# RelayBoard.net
KiCad netlist of a schematic drawn in EAGLE
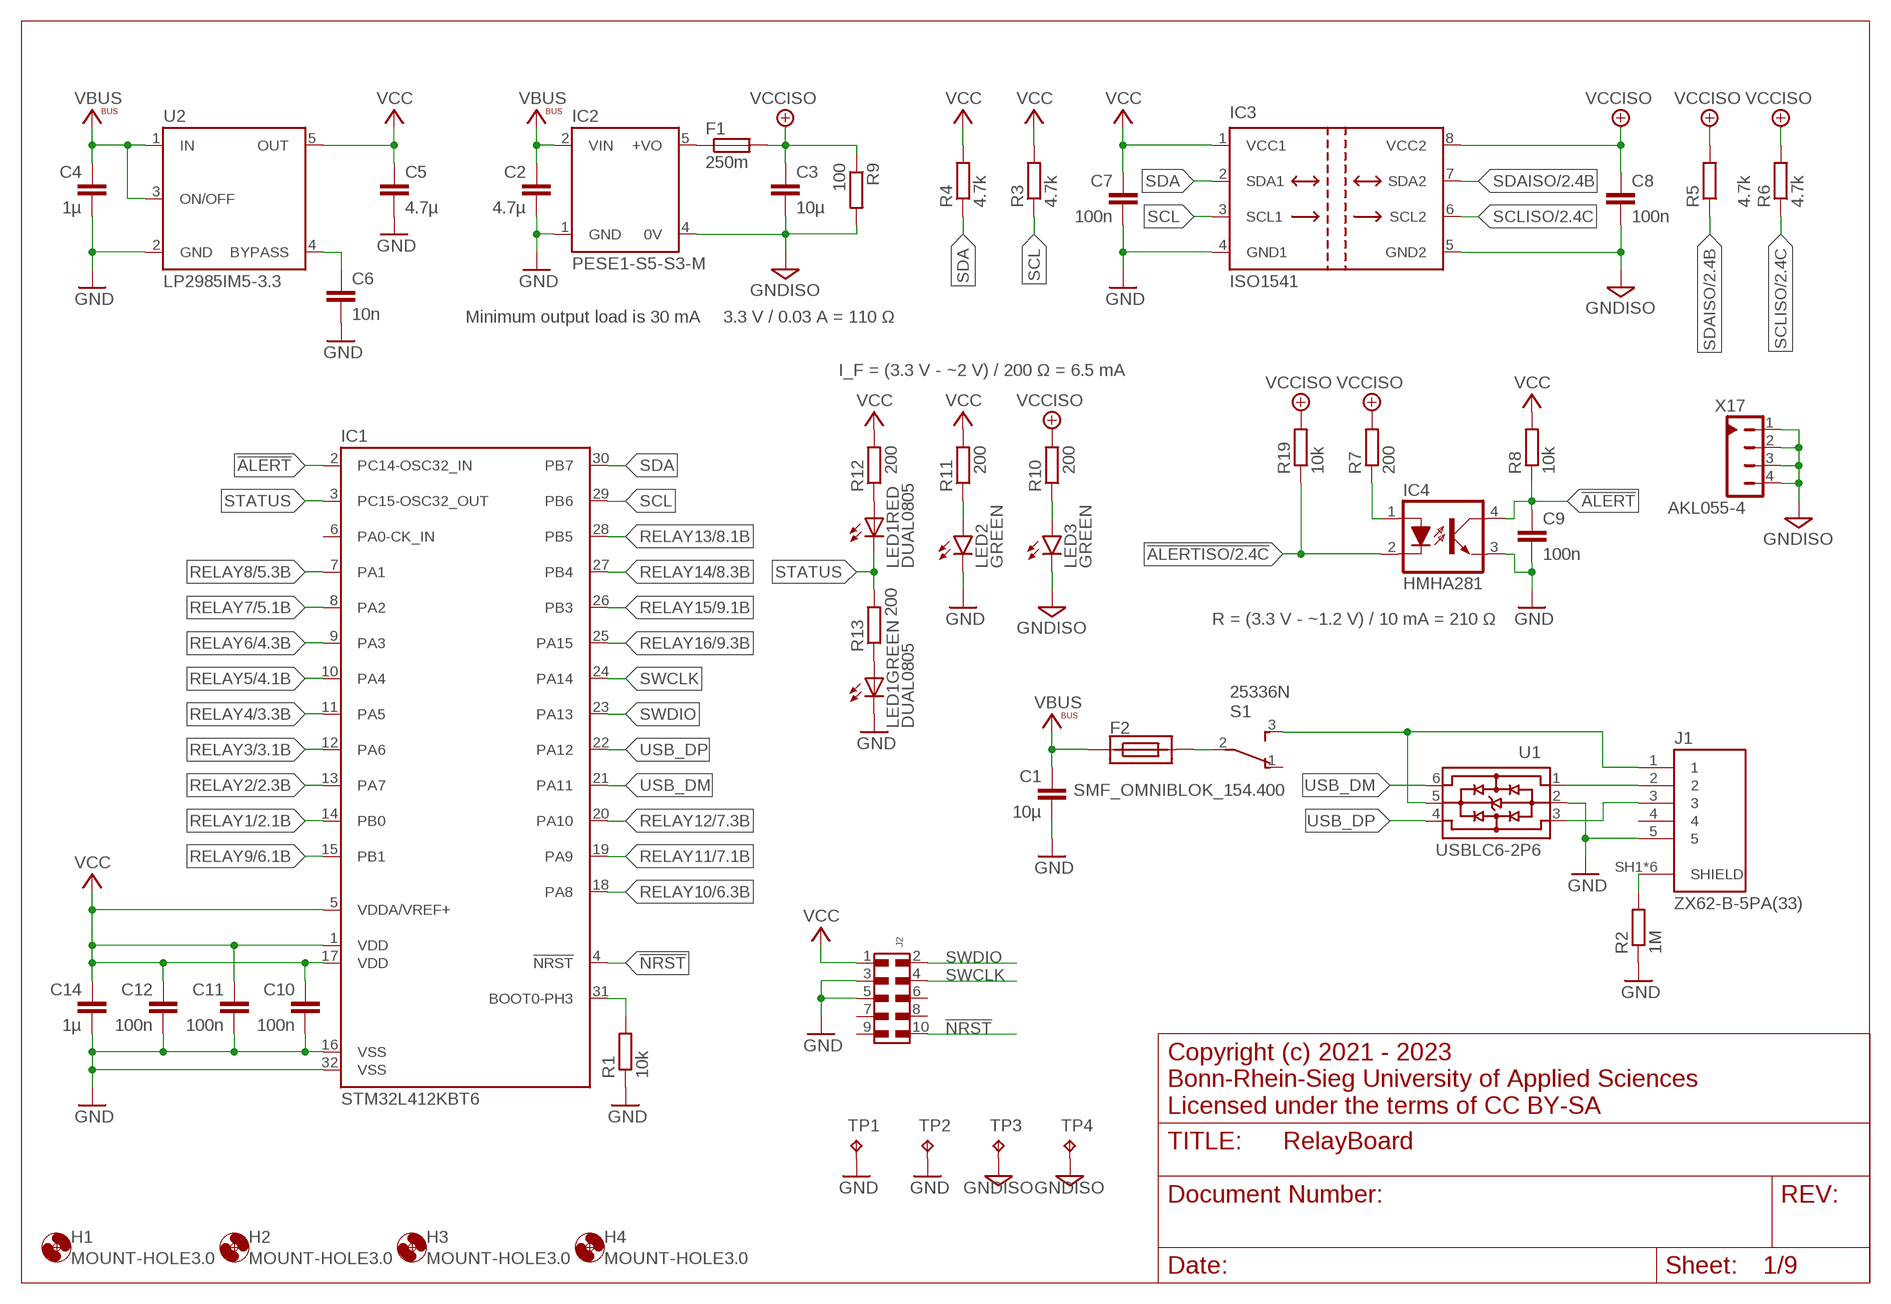
[diagram p0: schematic, sheet 1]
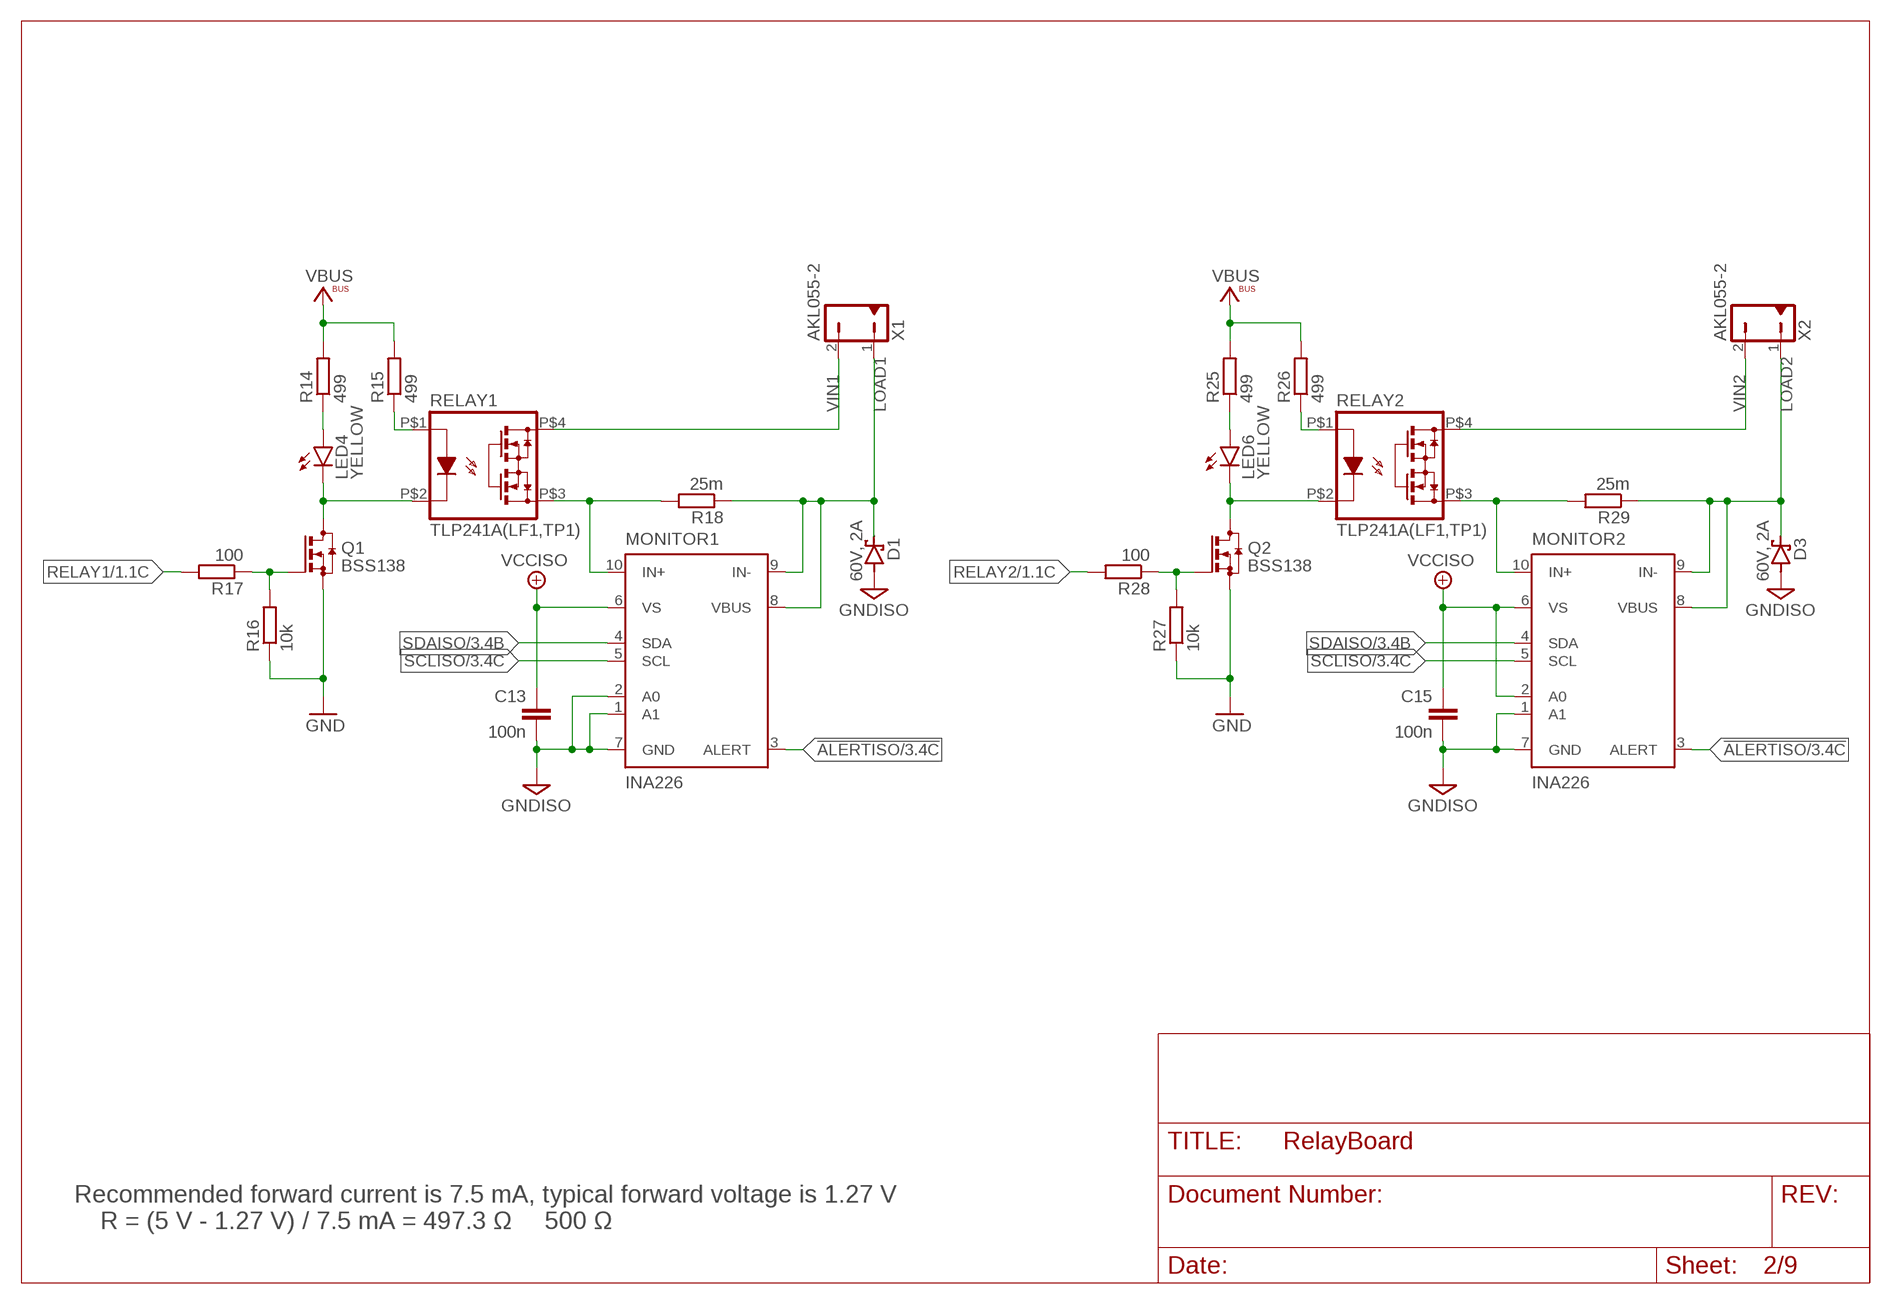
[diagram p1: schematic, sheet 2]
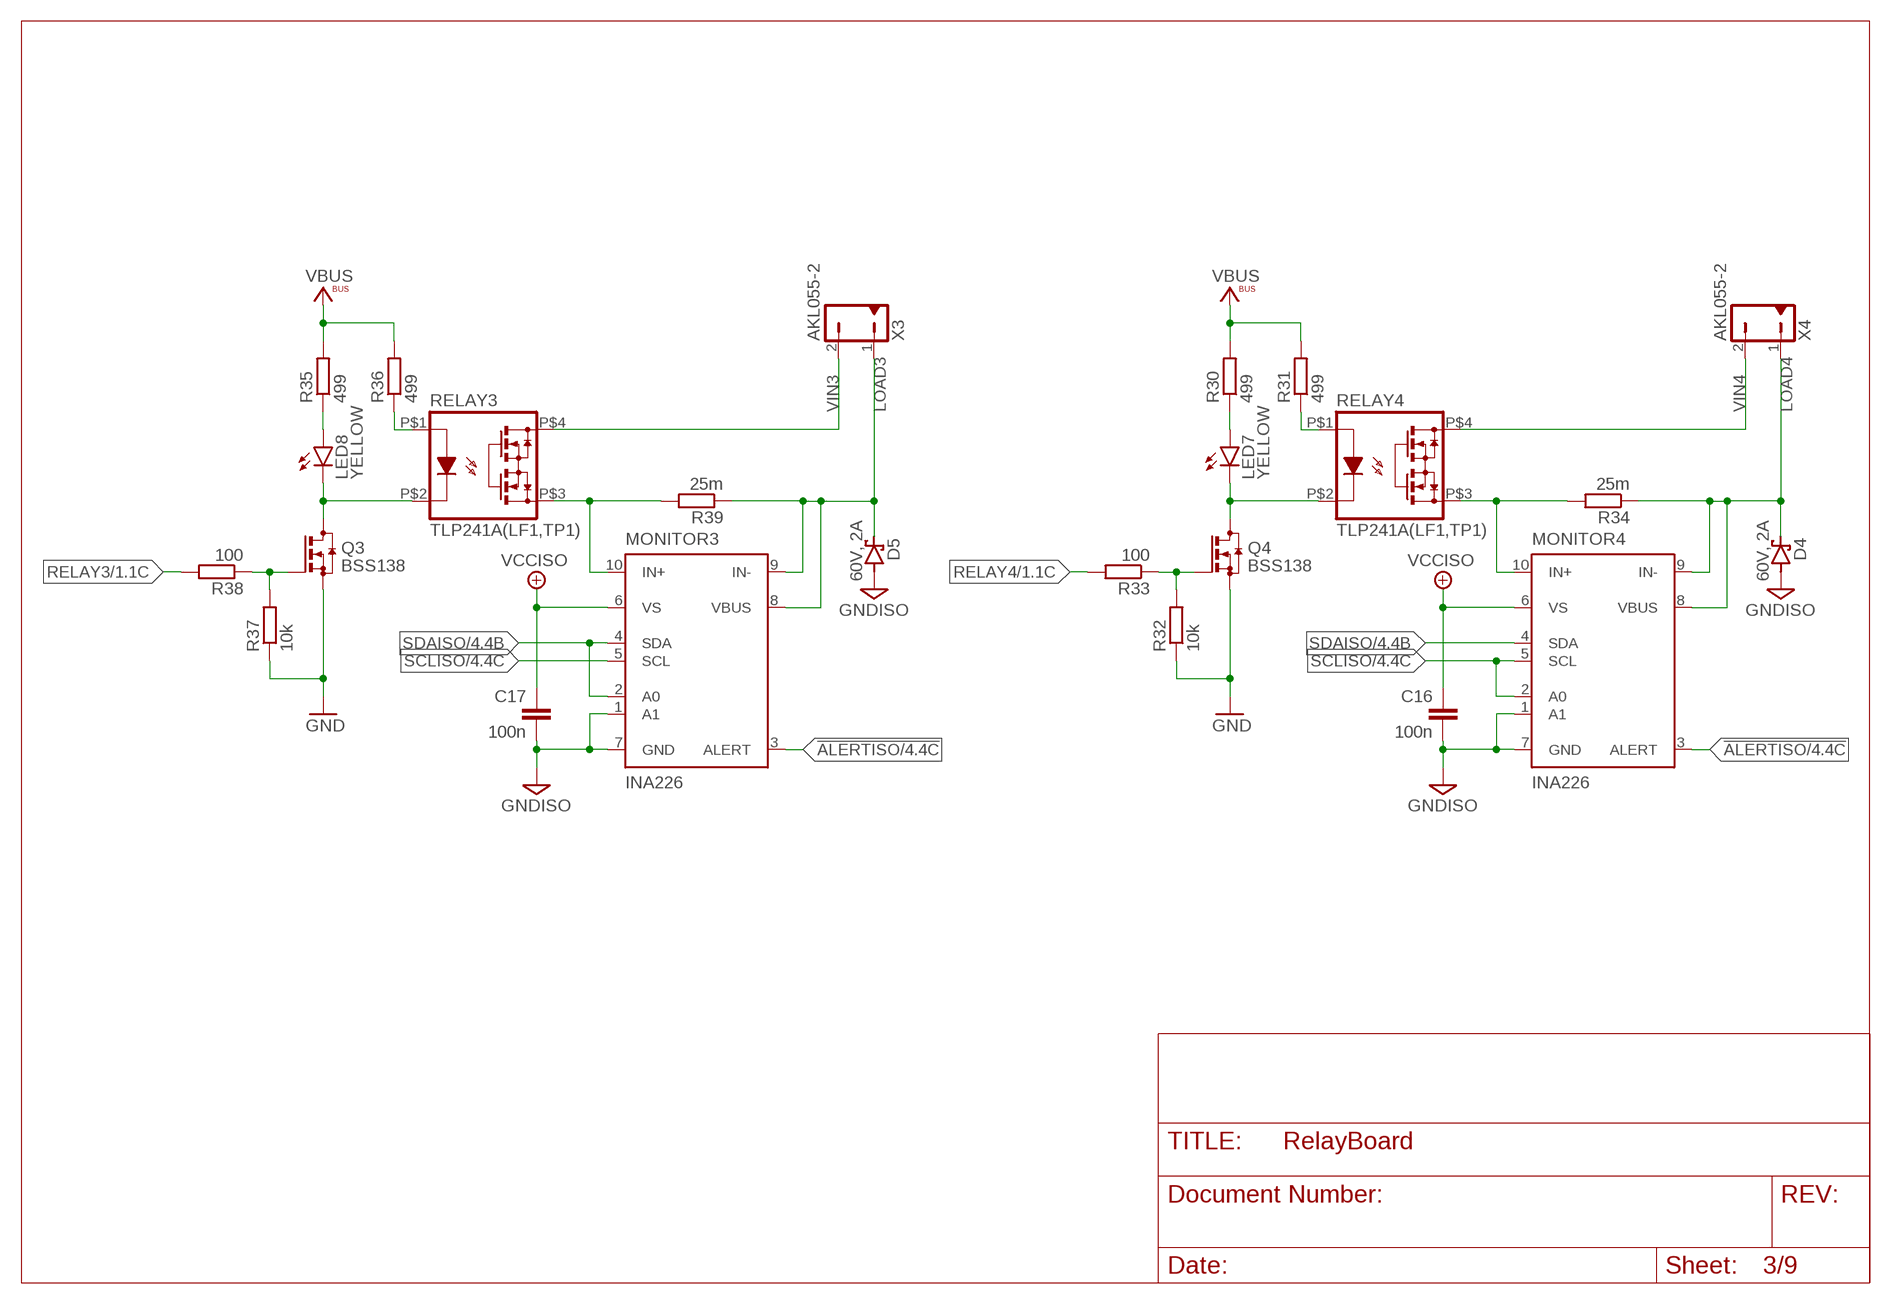
[diagram p2: schematic, sheet 3]
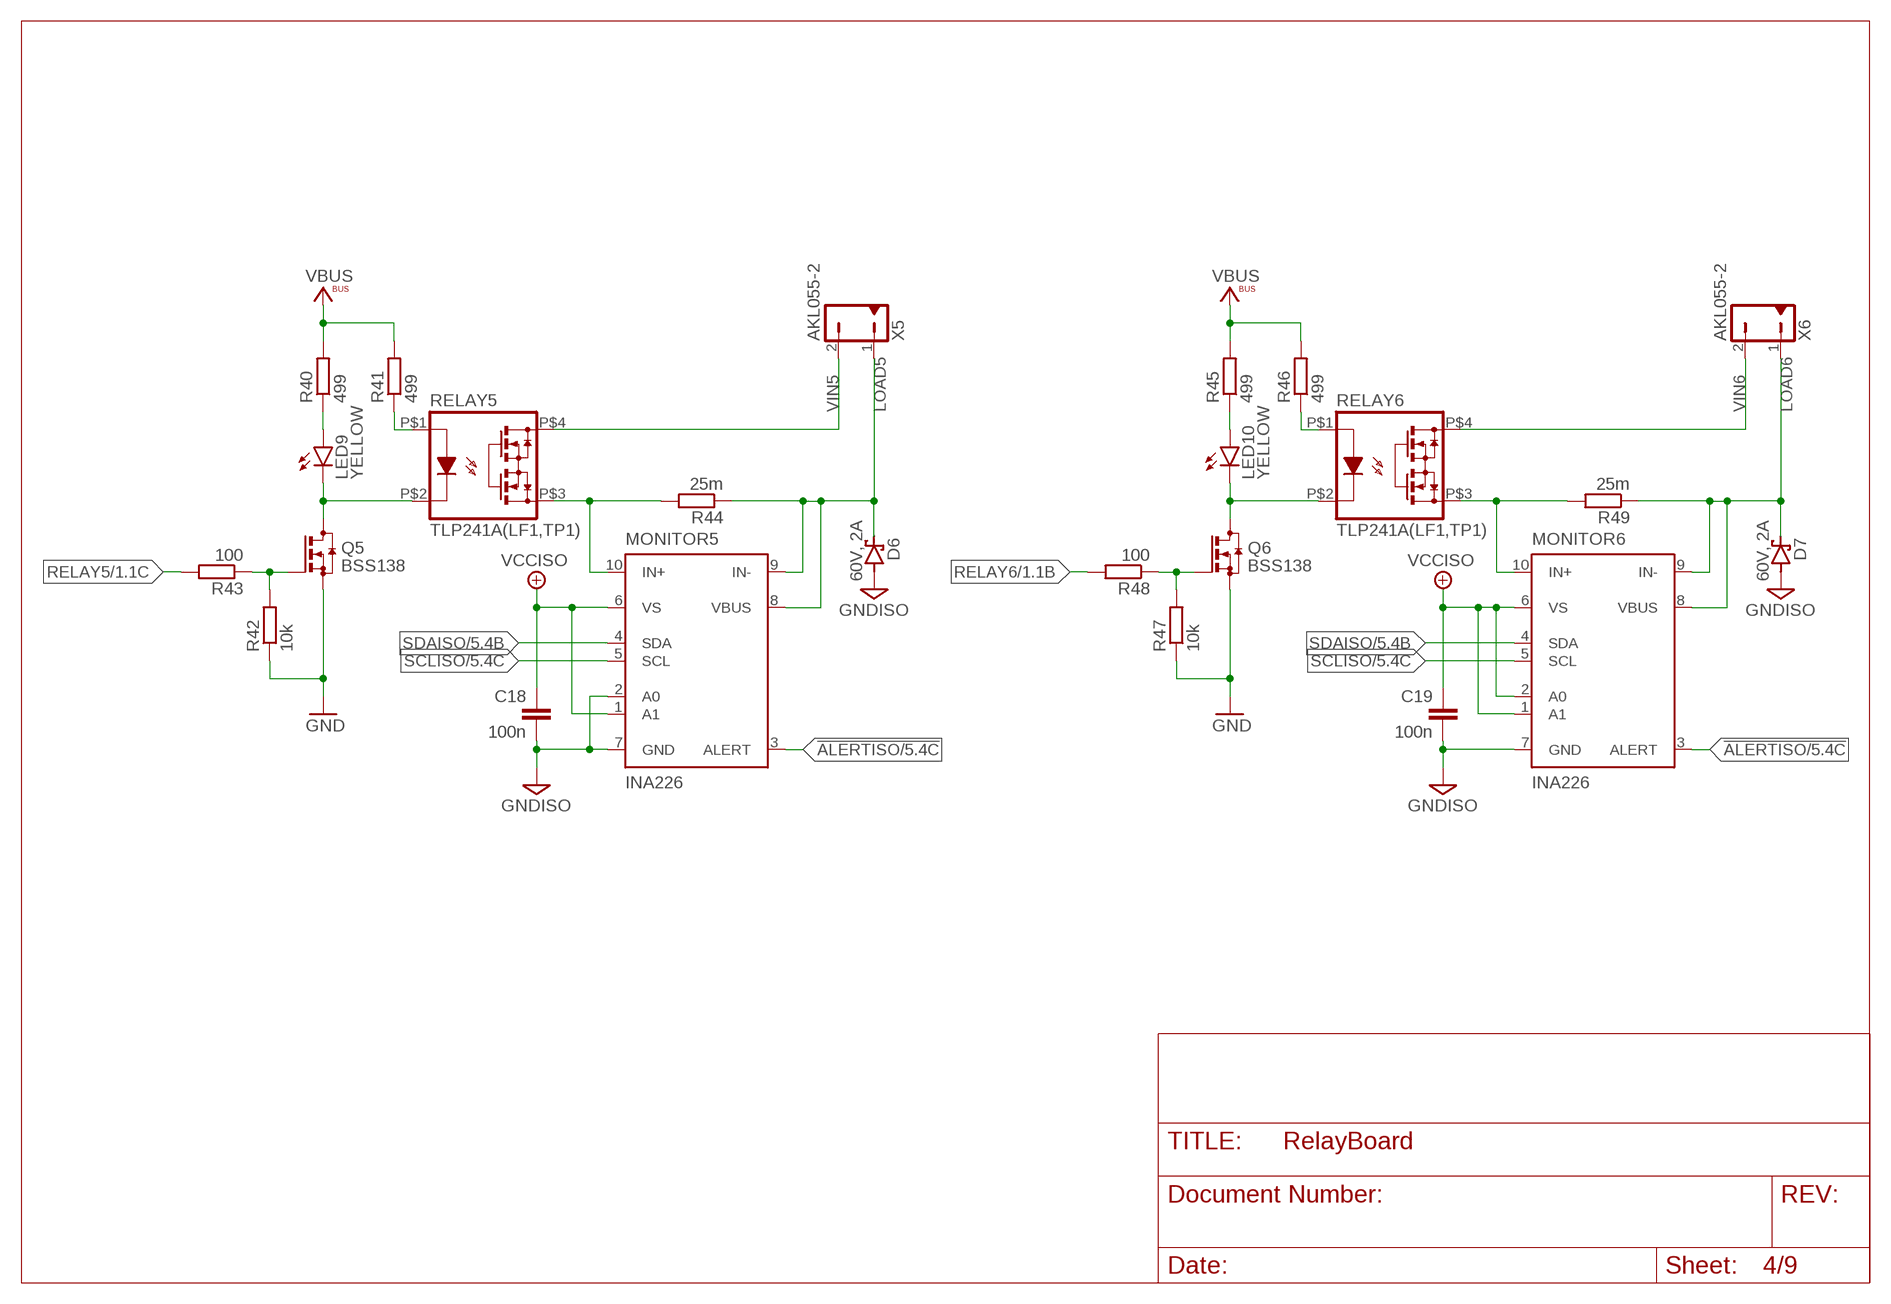
[diagram p3: schematic, sheet 4]
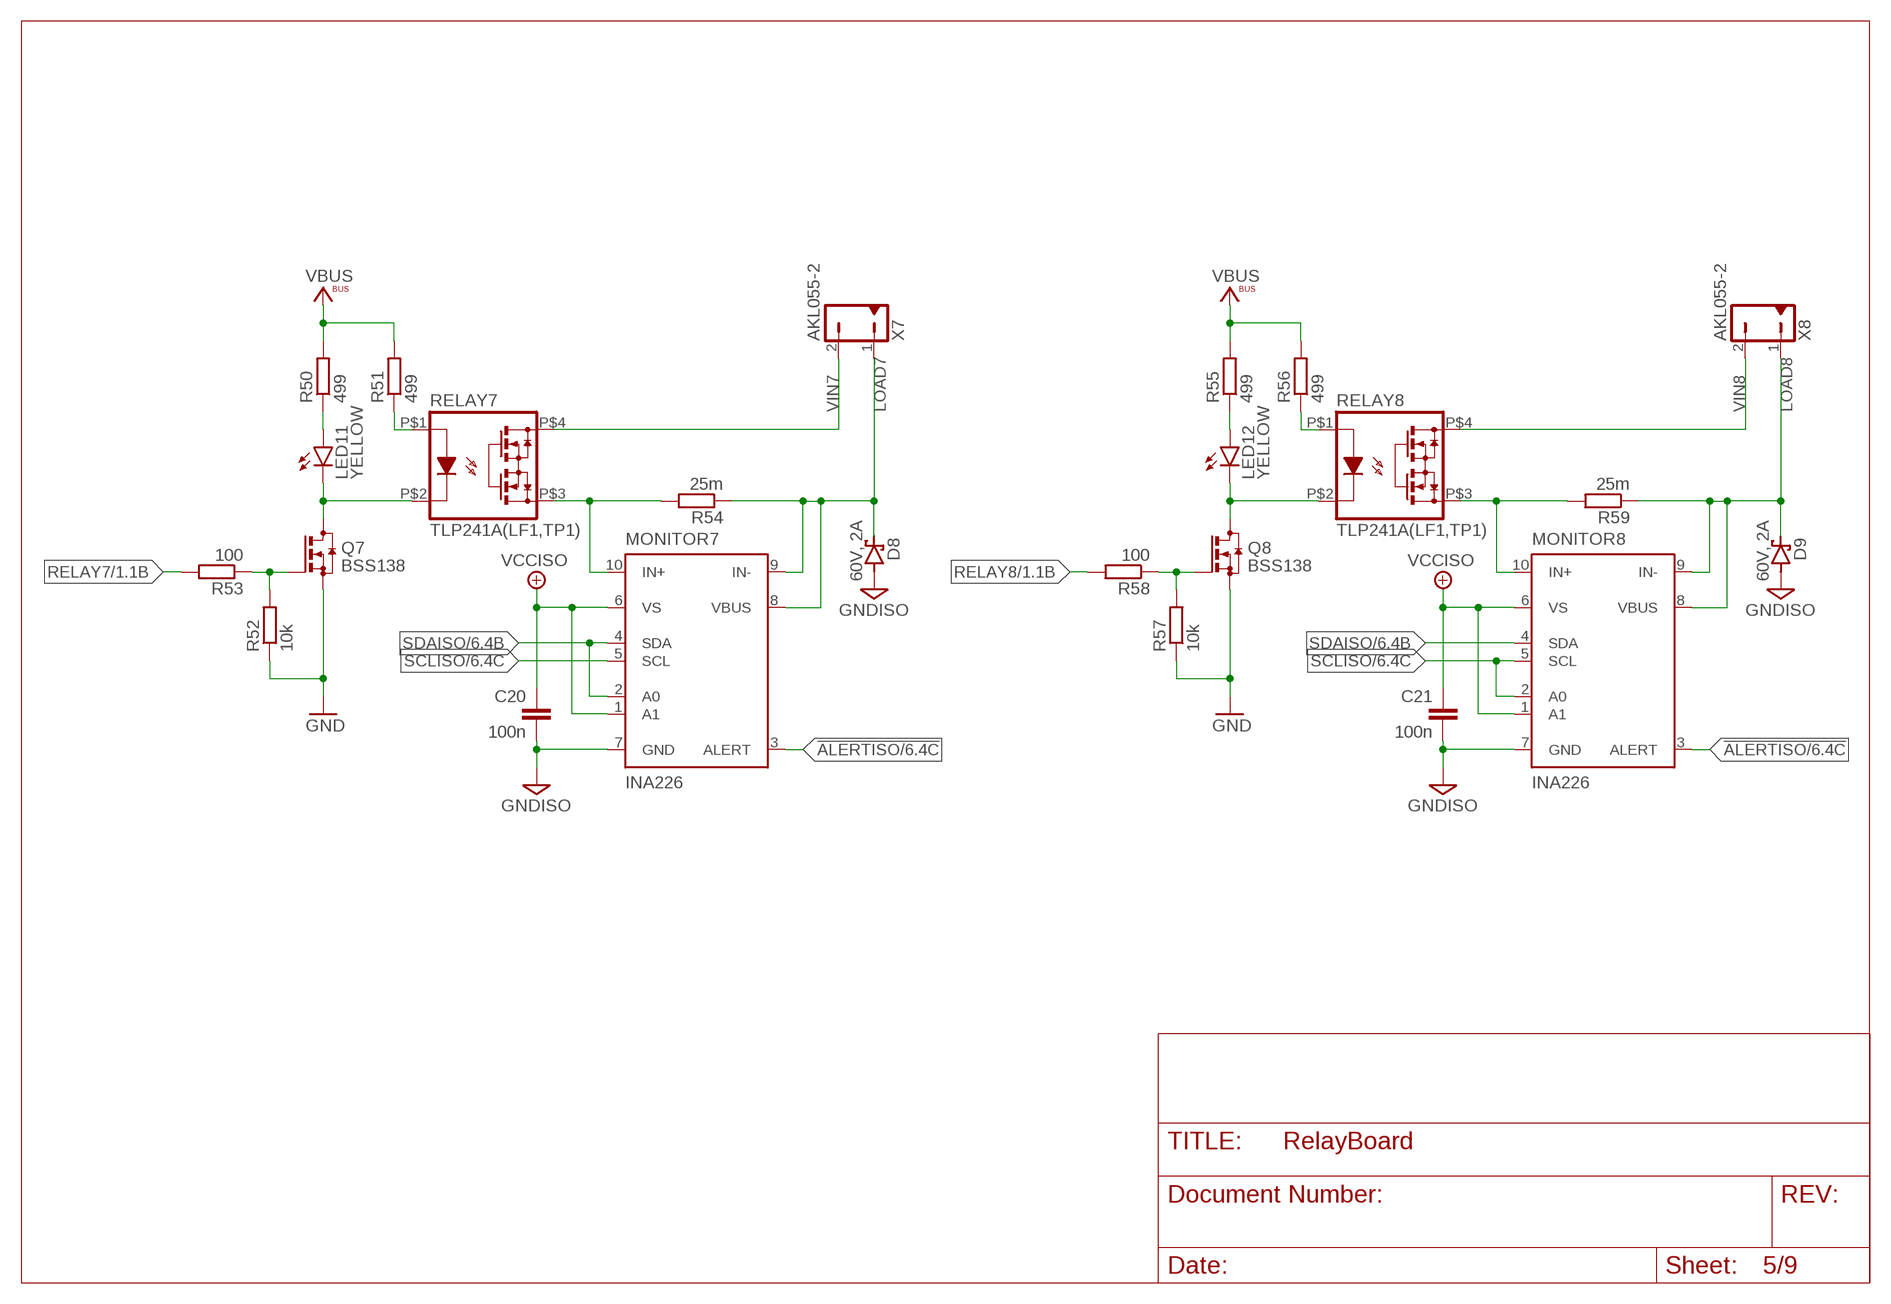
[diagram p4: schematic, sheet 5]
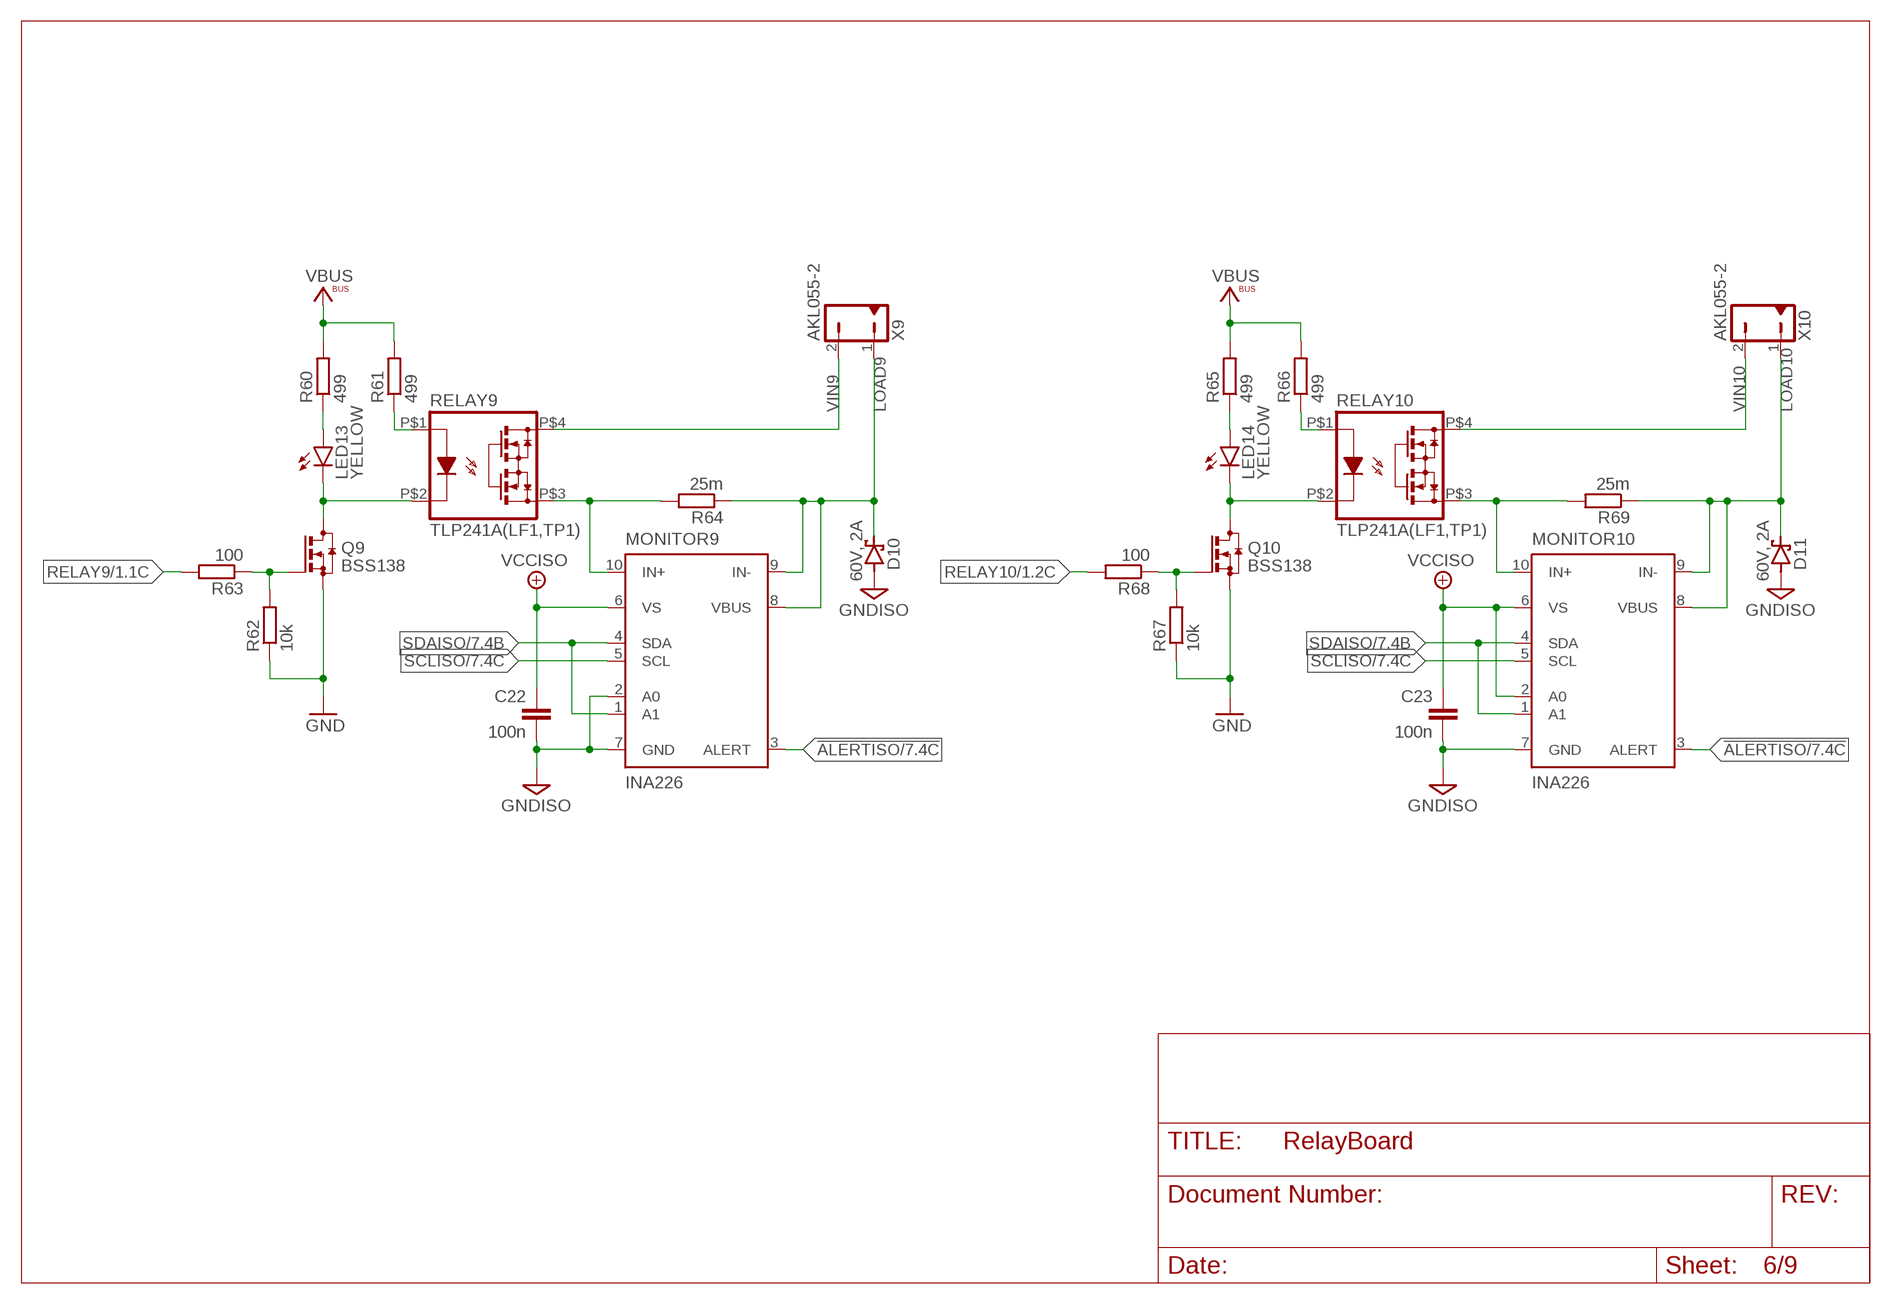
[diagram p5: schematic, sheet 6]
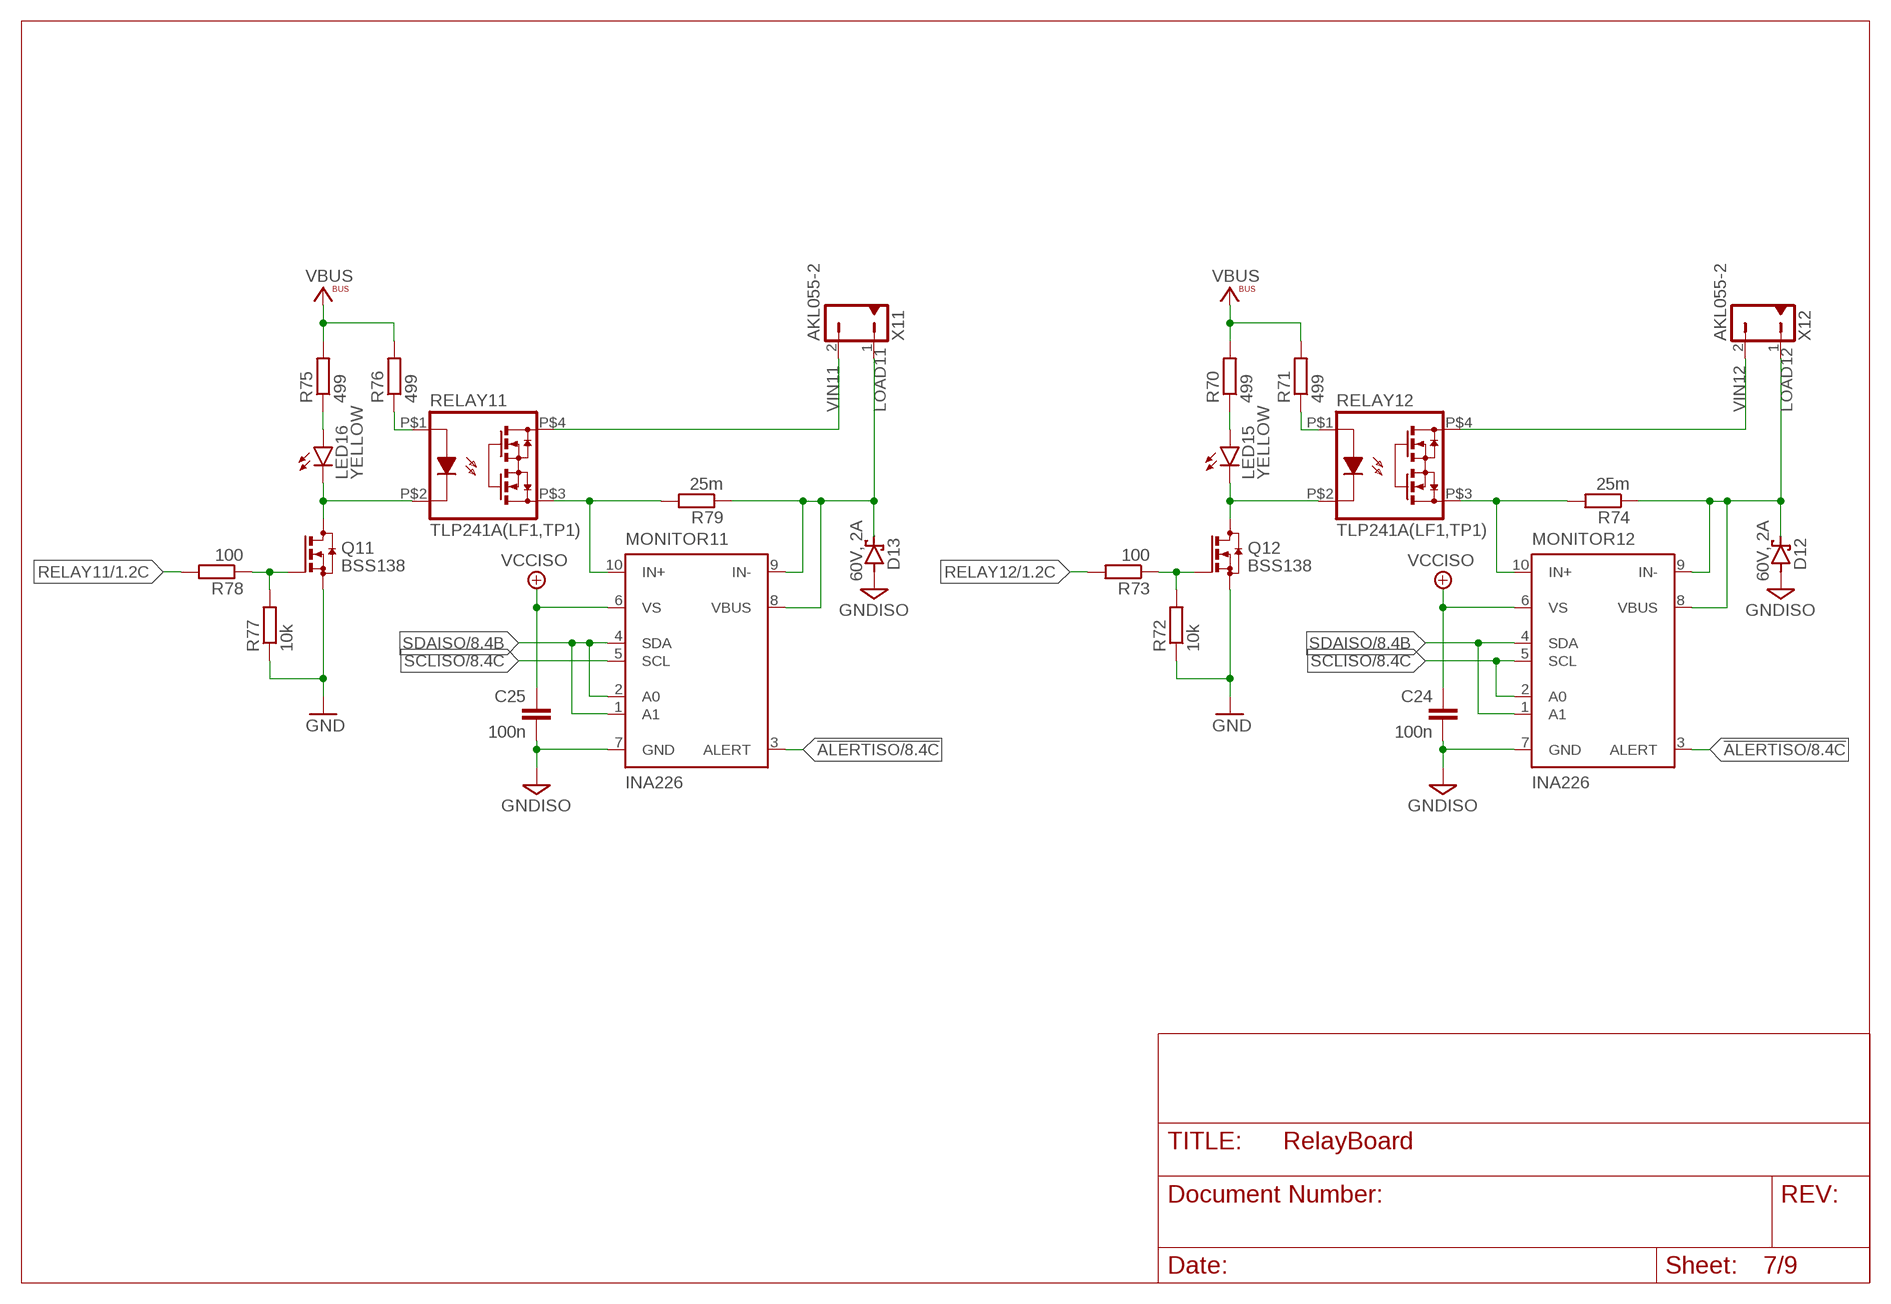
[diagram p6: schematic, sheet 7]
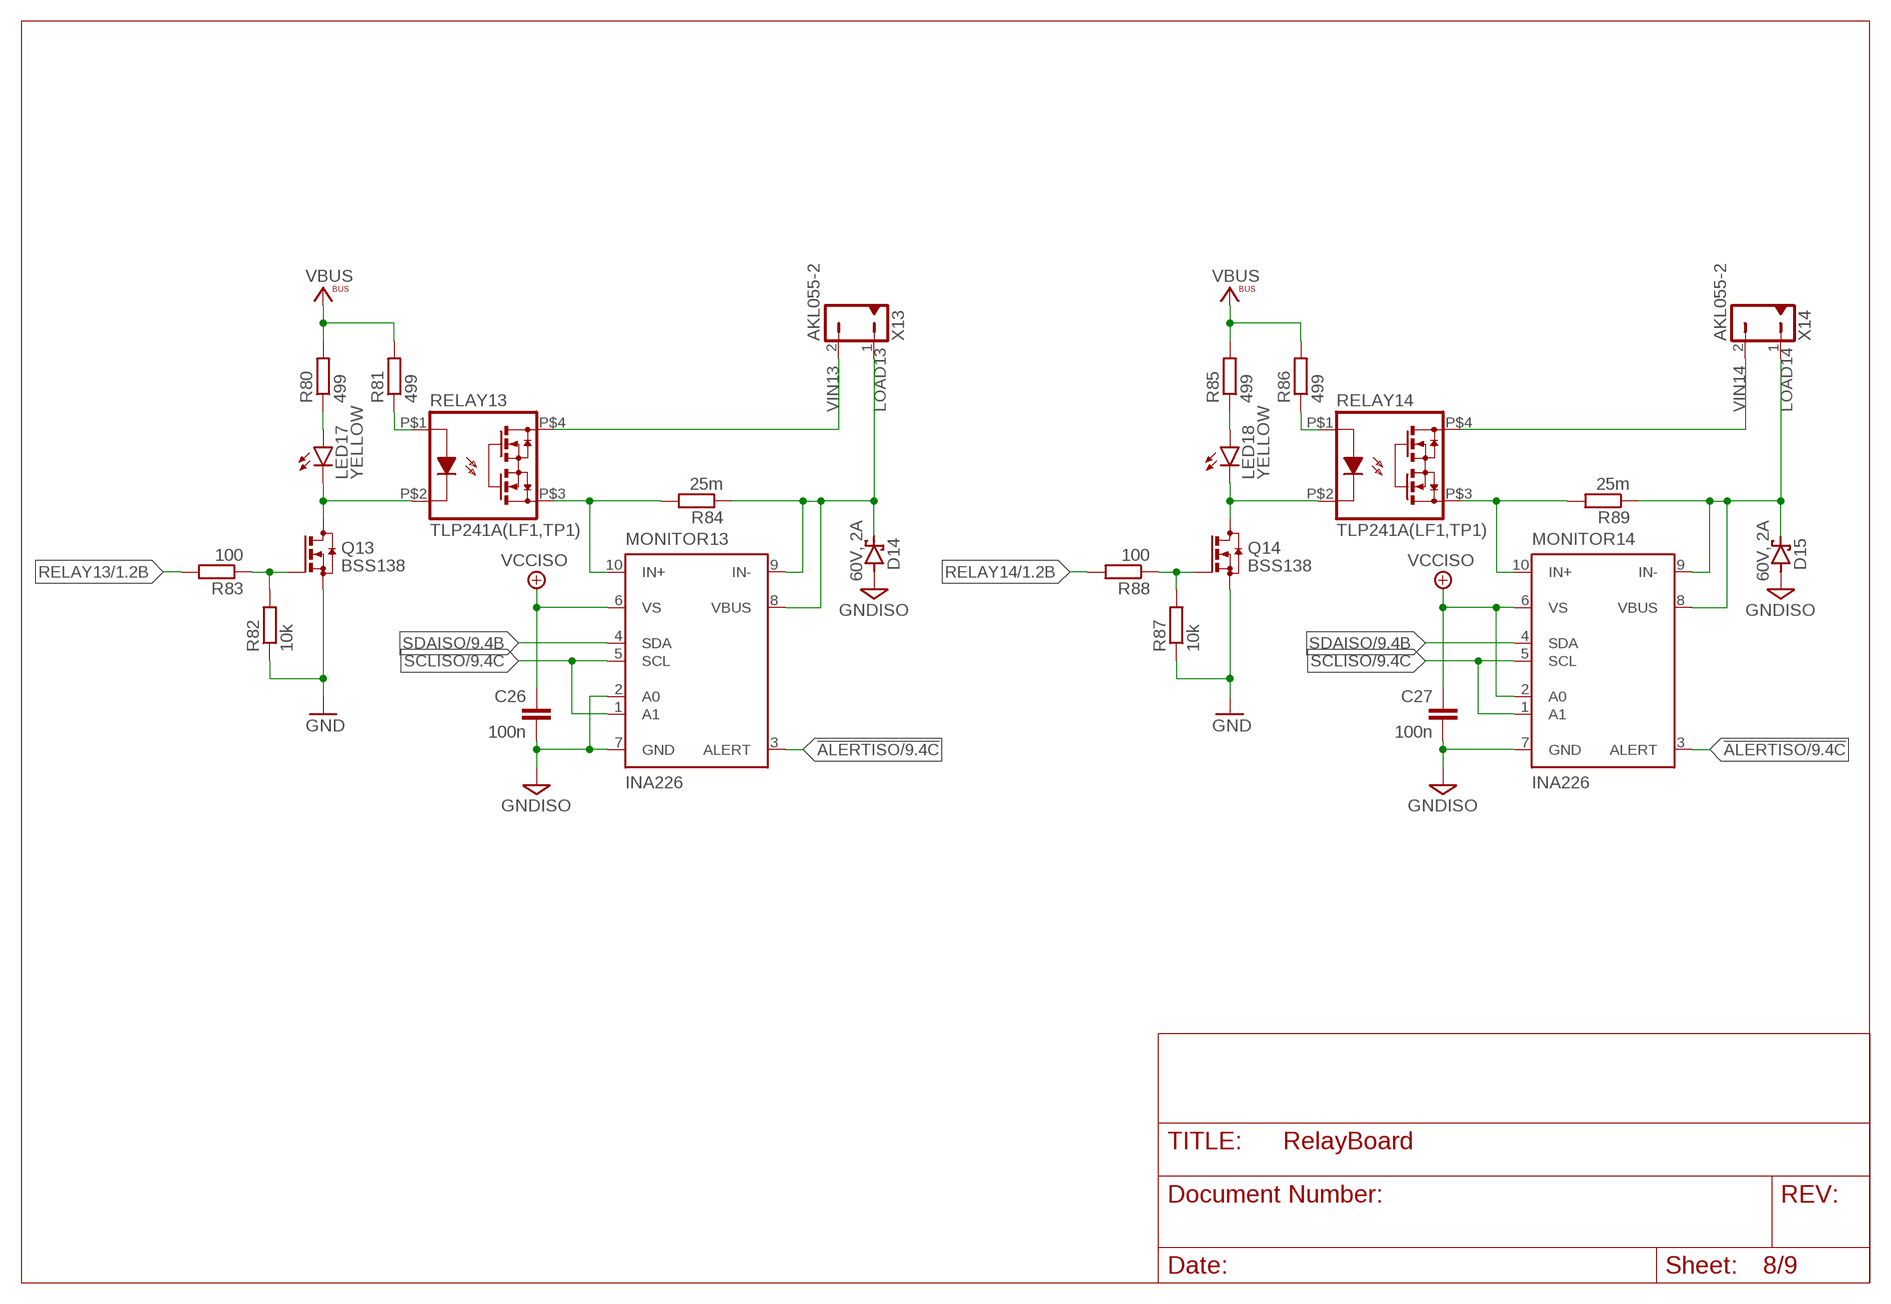
[diagram p7: schematic, sheet 8]
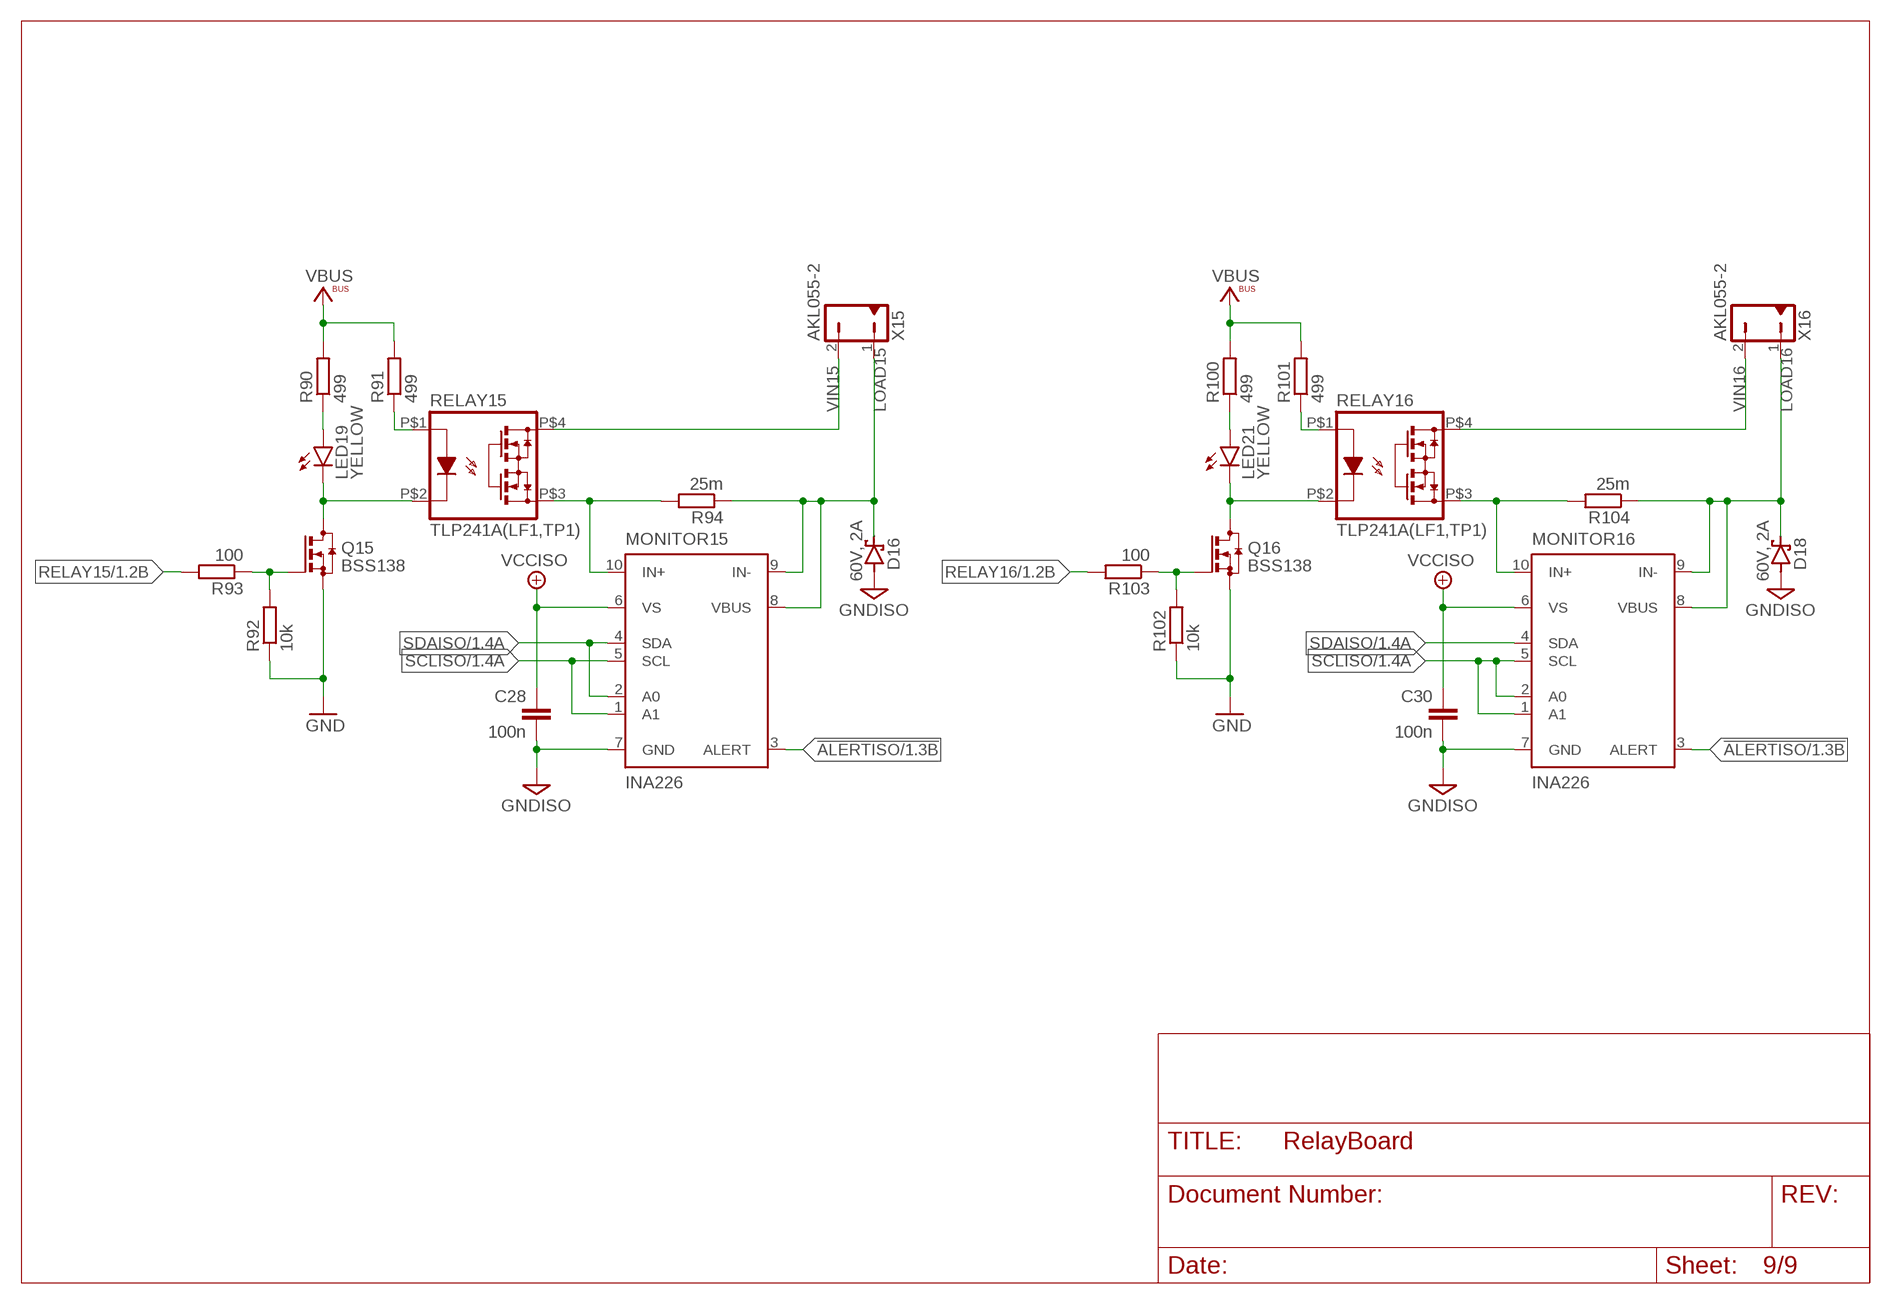
[diagram p8: schematic, sheet 9]

(export (version "E")
  (design (tool "Eeschema 10.0.6"))
  (components
    (comp (ref "C13")
      (value "100n")
      (footprint "eagle-import:C0603")
      (libsource (lib "eagle-import") (part "C-EUC0603"))
    )
    (comp (ref "C15")
      (value "100n")
      (footprint "eagle-import:C0603")
      (libsource (lib "eagle-import") (part "C-EUC0603"))
    )
    (comp (ref "D1")
      (value "60V, 2A")
      (footprint "eagle-import:SMB")
      (libsource (lib "eagle-import") (part "SCHOTTKY-DIODESMD"))
    )
    (comp (ref "D3")
      (value "60V, 2A")
      (footprint "eagle-import:SMB")
      (libsource (lib "eagle-import") (part "SCHOTTKY-DIODESMD"))
    )
    (comp (ref "LED4")
      (value "YELLOW")
      (footprint "eagle-import:CHIPLED_0805")
      (libsource (lib "eagle-import") (part "LEDCHIPLED_0805"))
    )
    (comp (ref "LED6")
      (value "YELLOW")
      (footprint "eagle-import:CHIPLED_0805")
      (libsource (lib "eagle-import") (part "LEDCHIPLED_0805"))
    )
    (comp (ref "MONITOR1")
      (value "INA226")
      (footprint "eagle-import:MSOP10")
      (libsource (lib "eagle-import") (part "INA226"))
    )
    (comp (ref "MONITOR2")
      (value "INA226")
      (footprint "eagle-import:MSOP10")
      (libsource (lib "eagle-import") (part "INA226"))
    )
    (comp (ref "Q1")
      (value "BSS138")
      (footprint "eagle-import:SOT23")
      (libsource (lib "eagle-import") (part "BSS138"))
    )
    (comp (ref "Q2")
      (value "BSS138")
      (footprint "eagle-import:SOT23")
      (libsource (lib "eagle-import") (part "BSS138"))
    )
    (comp (ref "R14")
      (value "499")
      (footprint "eagle-import:R0603")
      (libsource (lib "eagle-import") (part "R-EU_R0603"))
    )
    (comp (ref "R15")
      (value "499")
      (footprint "eagle-import:R0603")
      (libsource (lib "eagle-import") (part "R-EU_R0603"))
    )
    (comp (ref "R16")
      (value "10k")
      (footprint "eagle-import:R0603")
      (libsource (lib "eagle-import") (part "R-EU_R0603"))
    )
    (comp (ref "R17")
      (value "100")
      (footprint "eagle-import:R0603")
      (libsource (lib "eagle-import") (part "R-EU_R0603"))
    )
    (comp (ref "R18")
      (value "25m")
      (footprint "eagle-import:R1206")
      (libsource (lib "eagle-import") (part "R-EU_R1206"))
    )
    (comp (ref "R25")
      (value "499")
      (footprint "eagle-import:R0603")
      (libsource (lib "eagle-import") (part "R-EU_R0603"))
    )
    (comp (ref "R26")
      (value "499")
      (footprint "eagle-import:R0603")
      (libsource (lib "eagle-import") (part "R-EU_R0603"))
    )
    (comp (ref "R27")
      (value "10k")
      (footprint "eagle-import:R0603")
      (libsource (lib "eagle-import") (part "R-EU_R0603"))
    )
    (comp (ref "R28")
      (value "100")
      (footprint "eagle-import:R0603")
      (libsource (lib "eagle-import") (part "R-EU_R0603"))
    )
    (comp (ref "R29")
      (value "25m")
      (footprint "eagle-import:R1206")
      (libsource (lib "eagle-import") (part "R-EU_R1206"))
    )
    (comp (ref "RELAY1")
      (value "TLP241A(LF1,TP1)")
      (footprint "eagle-import:TP1_5")
      (libsource (lib "eagle-import") (part "TLP241A(?)LF1,TP1"))
    )
    (comp (ref "RELAY2")
      (value "TLP241A(LF1,TP1)")
      (footprint "eagle-import:TP1_5")
      (libsource (lib "eagle-import") (part "TLP241A(?)LF1,TP1"))
    )
    (comp (ref "X1")
      (value "AKL055-2")
      (footprint "eagle-import:AKL055-2")
      (libsource (lib "eagle-import") (part "AKL055-2"))
    )
    (comp (ref "X2")
      (value "AKL055-2")
      (footprint "eagle-import:AKL055-2")
      (libsource (lib "eagle-import") (part "AKL055-2"))
    )
    (comp (ref "C1")
      (value "10µ")
      (footprint "eagle-import:C0805")
      (libsource (lib "eagle-import") (part "C-EUC0805"))
    )
    (comp (ref "C2")
      (value "4.7µ")
      (footprint "eagle-import:C0805")
      (libsource (lib "eagle-import") (part "C-EUC0805"))
    )
    (comp (ref "C3")
      (value "10µ")
      (footprint "eagle-import:C0805")
      (libsource (lib "eagle-import") (part "C-EUC0805"))
    )
    (comp (ref "C4")
      (value "1µ")
      (footprint "eagle-import:C0805")
      (libsource (lib "eagle-import") (part "C-EUC0805"))
    )
    (comp (ref "C5")
      (value "4.7µ")
      (footprint "eagle-import:C0805")
      (libsource (lib "eagle-import") (part "C-EUC0805"))
    )
    (comp (ref "C6")
      (value "10n")
      (footprint "eagle-import:C0603")
      (libsource (lib "eagle-import") (part "C-EUC0603"))
    )
    (comp (ref "C7")
      (value "100n")
      (footprint "eagle-import:C0603")
      (libsource (lib "eagle-import") (part "C-EUC0603"))
    )
    (comp (ref "C8")
      (value "100n")
      (footprint "eagle-import:C0603")
      (libsource (lib "eagle-import") (part "C-EUC0603"))
    )
    (comp (ref "C9")
      (value "100n")
      (footprint "eagle-import:C0603")
      (libsource (lib "eagle-import") (part "C-EUC0603"))
    )
    (comp (ref "C10")
      (value "100n")
      (footprint "eagle-import:C0603")
      (libsource (lib "eagle-import") (part "C-EUC0603"))
    )
    (comp (ref "C11")
      (value "100n")
      (footprint "eagle-import:C0603")
      (libsource (lib "eagle-import") (part "C-EUC0603"))
    )
    (comp (ref "C12")
      (value "100n")
      (footprint "eagle-import:C0603")
      (libsource (lib "eagle-import") (part "C-EUC0603"))
    )
    (comp (ref "C14")
      (value "1µ")
      (footprint "eagle-import:C0603")
      (libsource (lib "eagle-import") (part "C-EUC0603"))
    )
    (comp (ref "F1")
      (value "250m")
      (footprint "eagle-import:R0603")
      (libsource (lib "eagle-import") (part "FUSE0603"))
    )
    (comp (ref "F2")
      (value "SMF_OMNIBLOK_154.400")
      (footprint "eagle-import:NANO2_SMF_FUSEBLOCK")
      (libsource (lib "eagle-import") (part "SMF_OMNIBLOK_154.400"))
    )
    (comp (ref "H1")
      (value "MOUNT-HOLE3.0")
      (footprint "eagle-import:3,0")
      (libsource (lib "eagle-import") (part "MOUNT-HOLE3.0"))
    )
    (comp (ref "H2")
      (value "MOUNT-HOLE3.0")
      (footprint "eagle-import:3,0")
      (libsource (lib "eagle-import") (part "MOUNT-HOLE3.0"))
    )
    (comp (ref "H3")
      (value "MOUNT-HOLE3.0")
      (footprint "eagle-import:3,0")
      (libsource (lib "eagle-import") (part "MOUNT-HOLE3.0"))
    )
    (comp (ref "H4")
      (value "MOUNT-HOLE3.0")
      (footprint "eagle-import:3,0")
      (libsource (lib "eagle-import") (part "MOUNT-HOLE3.0"))
    )
    (comp (ref "IC1")
      (value "STM32L412KBT6")
      (footprint "eagle-import:LQFP32")
      (libsource (lib "eagle-import") (part "STM32L412K?T6B"))
    )
    (comp (ref "IC2")
      (value "PESE1-S5-S3-M")
      (footprint "eagle-import:PESE1-M")
      (libsource (lib "eagle-import") (part "PESE1-S5-S-M3"))
    )
    (comp (ref "IC3")
      (value "ISO1541")
      (footprint "eagle-import:SOIC8")
      (libsource (lib "eagle-import") (part "ISO1541"))
    )
    (comp (ref "IC4")
      (value "HMHA281")
      (footprint "eagle-import:4-MINI-FLAT")
      (libsource (lib "eagle-import") (part "HMHA281"))
    )
    (comp (ref "J1")
      (value "ZX62-B-5PA(33)")
      (footprint "eagle-import:HRS_ZX62-B-5PA(33)")
      (fields (field (name "DIGI-KEY_PART_NUMBER") "H125270CT-ND") (field (name "MF") "Hirose"))
      (libsource (lib "eagle-import") (part "ZX62-B-5PA(33)"))
    )
    (comp (ref "J2")
      (value "6210XX21021_62101021021")
      (footprint "eagle-import:62101021021")
      (libsource (lib "eagle-import") (part "6210XX21021_62101021021"))
    )
    (comp (ref "LED1")
      (value "DUAL0805")
      (footprint "eagle-import:CHIPLEDX2")
      (libsource (lib "eagle-import") (part "DUAL0805"))
    )
    (comp (ref "LED2")
      (value "GREEN")
      (footprint "eagle-import:CHIPLED_0805")
      (libsource (lib "eagle-import") (part "LEDCHIPLED_0805"))
    )
    (comp (ref "LED3")
      (value "GREEN")
      (footprint "eagle-import:CHIPLED_0805")
      (libsource (lib "eagle-import") (part "LEDCHIPLED_0805"))
    )
    (comp (ref "R1")
      (value "10k")
      (footprint "eagle-import:R0603")
      (libsource (lib "eagle-import") (part "R-EU_R0603"))
    )
    (comp (ref "R2")
      (value "1M")
      (footprint "eagle-import:R0603")
      (libsource (lib "eagle-import") (part "R-EU_R0603"))
    )
    (comp (ref "R3")
      (value "4.7k")
      (footprint "eagle-import:R0603")
      (libsource (lib "eagle-import") (part "R-EU_R0603"))
    )
    (comp (ref "R4")
      (value "4.7k")
      (footprint "eagle-import:R0603")
      (libsource (lib "eagle-import") (part "R-EU_R0603"))
    )
    (comp (ref "R5")
      (value "4.7k")
      (footprint "eagle-import:R0603")
      (libsource (lib "eagle-import") (part "R-EU_R0603"))
    )
    (comp (ref "R6")
      (value "4.7k")
      (footprint "eagle-import:R0603")
      (libsource (lib "eagle-import") (part "R-EU_R0603"))
    )
    (comp (ref "R7")
      (value "200")
      (footprint "eagle-import:R0603")
      (libsource (lib "eagle-import") (part "R-EU_R0603"))
    )
    (comp (ref "R8")
      (value "10k")
      (footprint "eagle-import:R0603")
      (libsource (lib "eagle-import") (part "R-EU_R0603"))
    )
    (comp (ref "R9")
      (value "100")
      (footprint "eagle-import:R0603")
      (libsource (lib "eagle-import") (part "R-EU_R0603"))
    )
    (comp (ref "R10")
      (value "200")
      (footprint "eagle-import:R0603")
      (libsource (lib "eagle-import") (part "R-EU_R0603"))
    )
    (comp (ref "R11")
      (value "200")
      (footprint "eagle-import:R0603")
      (libsource (lib "eagle-import") (part "R-EU_R0603"))
    )
    (comp (ref "R12")
      (value "200")
      (footprint "eagle-import:R0603")
      (libsource (lib "eagle-import") (part "R-EU_R0603"))
    )
    (comp (ref "R13")
      (value "200")
      (footprint "eagle-import:R0603")
      (libsource (lib "eagle-import") (part "R-EU_R0603"))
    )
    (comp (ref "R19")
      (value "10k")
      (footprint "eagle-import:R0603")
      (libsource (lib "eagle-import") (part "R-EU_R0603"))
    )
    (comp (ref "S1")
      (value "25336N")
      (footprint "eagle-import:2533XN")
      (libsource (lib "eagle-import") (part "25336N"))
    )
    (comp (ref "TP1")
      (value "TP3.8X2.03")
      (footprint "eagle-import:3.8X2.03")
      (libsource (lib "eagle-import") (part "TP3.8X2.03"))
    )
    (comp (ref "TP2")
      (value "TP3.8X2.03")
      (footprint "eagle-import:3.8X2.03")
      (libsource (lib "eagle-import") (part "TP3.8X2.03"))
    )
    (comp (ref "TP3")
      (value "TP3.8X2.03")
      (footprint "eagle-import:3.8X2.03")
      (libsource (lib "eagle-import") (part "TP3.8X2.03"))
    )
    (comp (ref "TP4")
      (value "TP3.8X2.03")
      (footprint "eagle-import:3.8X2.03")
      (libsource (lib "eagle-import") (part "TP3.8X2.03"))
    )
    (comp (ref "U1")
      (value "USBLC6-2P6")
      (footprint "eagle-import:SOT-666")
      (libsource (lib "eagle-import") (part "USBLC6-2P6"))
    )
    (comp (ref "U2")
      (value "LP2985IM5-3.3")
      (footprint "eagle-import:SOT23-5")
      (libsource (lib "eagle-import") (part "LP2985?-IM53.3"))
    )
    (comp (ref "X17")
      (value "AKL055-4")
      (footprint "eagle-import:AKL055-4")
      (libsource (lib "eagle-import") (part "AKL055-4"))
    )
    (comp (ref "C16")
      (value "100n")
      (footprint "eagle-import:C0603")
      (libsource (lib "eagle-import") (part "C-EUC0603"))
    )
    (comp (ref "C17")
      (value "100n")
      (footprint "eagle-import:C0603")
      (libsource (lib "eagle-import") (part "C-EUC0603"))
    )
    (comp (ref "D4")
      (value "60V, 2A")
      (footprint "eagle-import:SMB")
      (libsource (lib "eagle-import") (part "SCHOTTKY-DIODESMD"))
    )
    (comp (ref "D5")
      (value "60V, 2A")
      (footprint "eagle-import:SMB")
      (libsource (lib "eagle-import") (part "SCHOTTKY-DIODESMD"))
    )
    (comp (ref "LED7")
      (value "YELLOW")
      (footprint "eagle-import:CHIPLED_0805")
      (libsource (lib "eagle-import") (part "LEDCHIPLED_0805"))
    )
    (comp (ref "LED8")
      (value "YELLOW")
      (footprint "eagle-import:CHIPLED_0805")
      (libsource (lib "eagle-import") (part "LEDCHIPLED_0805"))
    )
    (comp (ref "MONITOR3")
      (value "INA226")
      (footprint "eagle-import:MSOP10")
      (libsource (lib "eagle-import") (part "INA226"))
    )
    (comp (ref "MONITOR4")
      (value "INA226")
      (footprint "eagle-import:MSOP10")
      (libsource (lib "eagle-import") (part "INA226"))
    )
    (comp (ref "Q3")
      (value "BSS138")
      (footprint "eagle-import:SOT23")
      (libsource (lib "eagle-import") (part "BSS138"))
    )
    (comp (ref "Q4")
      (value "BSS138")
      (footprint "eagle-import:SOT23")
      (libsource (lib "eagle-import") (part "BSS138"))
    )
    (comp (ref "R30")
      (value "499")
      (footprint "eagle-import:R0603")
      (libsource (lib "eagle-import") (part "R-EU_R0603"))
    )
    (comp (ref "R31")
      (value "499")
      (footprint "eagle-import:R0603")
      (libsource (lib "eagle-import") (part "R-EU_R0603"))
    )
    (comp (ref "R32")
      (value "10k")
      (footprint "eagle-import:R0603")
      (libsource (lib "eagle-import") (part "R-EU_R0603"))
    )
    (comp (ref "R33")
      (value "100")
      (footprint "eagle-import:R0603")
      (libsource (lib "eagle-import") (part "R-EU_R0603"))
    )
    (comp (ref "R34")
      (value "25m")
      (footprint "eagle-import:R1206")
      (libsource (lib "eagle-import") (part "R-EU_R1206"))
    )
    (comp (ref "R35")
      (value "499")
      (footprint "eagle-import:R0603")
      (libsource (lib "eagle-import") (part "R-EU_R0603"))
    )
    (comp (ref "R36")
      (value "499")
      (footprint "eagle-import:R0603")
      (libsource (lib "eagle-import") (part "R-EU_R0603"))
    )
    (comp (ref "R37")
      (value "10k")
      (footprint "eagle-import:R0603")
      (libsource (lib "eagle-import") (part "R-EU_R0603"))
    )
    (comp (ref "R38")
      (value "100")
      (footprint "eagle-import:R0603")
      (libsource (lib "eagle-import") (part "R-EU_R0603"))
    )
    (comp (ref "R39")
      (value "25m")
      (footprint "eagle-import:R1206")
      (libsource (lib "eagle-import") (part "R-EU_R1206"))
    )
    (comp (ref "RELAY3")
      (value "TLP241A(LF1,TP1)")
      (footprint "eagle-import:TP1_5")
      (libsource (lib "eagle-import") (part "TLP241A(?)LF1,TP1"))
    )
    (comp (ref "RELAY4")
      (value "TLP241A(LF1,TP1)")
      (footprint "eagle-import:TP1_5")
      (libsource (lib "eagle-import") (part "TLP241A(?)LF1,TP1"))
    )
    (comp (ref "X3")
      (value "AKL055-2")
      (footprint "eagle-import:AKL055-2")
      (libsource (lib "eagle-import") (part "AKL055-2"))
    )
    (comp (ref "X4")
      (value "AKL055-2")
      (footprint "eagle-import:AKL055-2")
      (libsource (lib "eagle-import") (part "AKL055-2"))
    )
    (comp (ref "C26")
      (value "100n")
      (footprint "eagle-import:C0603")
      (libsource (lib "eagle-import") (part "C-EUC0603"))
    )
    (comp (ref "C27")
      (value "100n")
      (footprint "eagle-import:C0603")
      (libsource (lib "eagle-import") (part "C-EUC0603"))
    )
    (comp (ref "D14")
      (value "60V, 2A")
      (footprint "eagle-import:SMB")
      (libsource (lib "eagle-import") (part "SCHOTTKY-DIODESMD"))
    )
    (comp (ref "D15")
      (value "60V, 2A")
      (footprint "eagle-import:SMB")
      (libsource (lib "eagle-import") (part "SCHOTTKY-DIODESMD"))
    )
    (comp (ref "LED17")
      (value "YELLOW")
      (footprint "eagle-import:CHIPLED_0805")
      (libsource (lib "eagle-import") (part "LEDCHIPLED_0805"))
    )
    (comp (ref "LED18")
      (value "YELLOW")
      (footprint "eagle-import:CHIPLED_0805")
      (libsource (lib "eagle-import") (part "LEDCHIPLED_0805"))
    )
    (comp (ref "MONITOR13")
      (value "INA226")
      (footprint "eagle-import:MSOP10")
      (libsource (lib "eagle-import") (part "INA226"))
    )
    (comp (ref "MONITOR14")
      (value "INA226")
      (footprint "eagle-import:MSOP10")
      (libsource (lib "eagle-import") (part "INA226"))
    )
    (comp (ref "Q13")
      (value "BSS138")
      (footprint "eagle-import:SOT23")
      (libsource (lib "eagle-import") (part "BSS138"))
    )
    (comp (ref "Q14")
      (value "BSS138")
      (footprint "eagle-import:SOT23")
      (libsource (lib "eagle-import") (part "BSS138"))
    )
    (comp (ref "R80")
      (value "499")
      (footprint "eagle-import:R0603")
      (libsource (lib "eagle-import") (part "R-EU_R0603"))
    )
    (comp (ref "R81")
      (value "499")
      (footprint "eagle-import:R0603")
      (libsource (lib "eagle-import") (part "R-EU_R0603"))
    )
    (comp (ref "R82")
      (value "10k")
      (footprint "eagle-import:R0603")
      (libsource (lib "eagle-import") (part "R-EU_R0603"))
    )
    (comp (ref "R83")
      (value "100")
      (footprint "eagle-import:R0603")
      (libsource (lib "eagle-import") (part "R-EU_R0603"))
    )
    (comp (ref "R84")
      (value "25m")
      (footprint "eagle-import:R1206")
      (libsource (lib "eagle-import") (part "R-EU_R1206"))
    )
    (comp (ref "R85")
      (value "499")
      (footprint "eagle-import:R0603")
      (libsource (lib "eagle-import") (part "R-EU_R0603"))
    )
    (comp (ref "R86")
      (value "499")
      (footprint "eagle-import:R0603")
      (libsource (lib "eagle-import") (part "R-EU_R0603"))
    )
    (comp (ref "R87")
      (value "10k")
      (footprint "eagle-import:R0603")
      (libsource (lib "eagle-import") (part "R-EU_R0603"))
    )
    (comp (ref "R88")
      (value "100")
      (footprint "eagle-import:R0603")
      (libsource (lib "eagle-import") (part "R-EU_R0603"))
    )
    (comp (ref "R89")
      (value "25m")
      (footprint "eagle-import:R1206")
      (libsource (lib "eagle-import") (part "R-EU_R1206"))
    )
    (comp (ref "RELAY13")
      (value "TLP241A(LF1,TP1)")
      (footprint "eagle-import:TP1_5")
      (libsource (lib "eagle-import") (part "TLP241A(?)LF1,TP1"))
    )
    (comp (ref "RELAY14")
      (value "TLP241A(LF1,TP1)")
      (footprint "eagle-import:TP1_5")
      (libsource (lib "eagle-import") (part "TLP241A(?)LF1,TP1"))
    )
    (comp (ref "X13")
      (value "AKL055-2")
      (footprint "eagle-import:AKL055-2")
      (libsource (lib "eagle-import") (part "AKL055-2"))
    )
    (comp (ref "X14")
      (value "AKL055-2")
      (footprint "eagle-import:AKL055-2")
      (libsource (lib "eagle-import") (part "AKL055-2"))
    )
    (comp (ref "C28")
      (value "100n")
      (footprint "eagle-import:C0603")
      (libsource (lib "eagle-import") (part "C-EUC0603"))
    )
    (comp (ref "C30")
      (value "100n")
      (footprint "eagle-import:C0603")
      (libsource (lib "eagle-import") (part "C-EUC0603"))
    )
    (comp (ref "D16")
      (value "60V, 2A")
      (footprint "eagle-import:SMB")
      (libsource (lib "eagle-import") (part "SCHOTTKY-DIODESMD"))
    )
    (comp (ref "D18")
      (value "60V, 2A")
      (footprint "eagle-import:SMB")
      (libsource (lib "eagle-import") (part "SCHOTTKY-DIODESMD"))
    )
    (comp (ref "LED19")
      (value "YELLOW")
      (footprint "eagle-import:CHIPLED_0805")
      (libsource (lib "eagle-import") (part "LEDCHIPLED_0805"))
    )
    (comp (ref "LED21")
      (value "YELLOW")
      (footprint "eagle-import:CHIPLED_0805")
      (libsource (lib "eagle-import") (part "LEDCHIPLED_0805"))
    )
    (comp (ref "MONITOR15")
      (value "INA226")
      (footprint "eagle-import:MSOP10")
      (libsource (lib "eagle-import") (part "INA226"))
    )
    (comp (ref "MONITOR16")
      (value "INA226")
      (footprint "eagle-import:MSOP10")
      (libsource (lib "eagle-import") (part "INA226"))
    )
    (comp (ref "Q15")
      (value "BSS138")
      (footprint "eagle-import:SOT23")
      (libsource (lib "eagle-import") (part "BSS138"))
    )
    (comp (ref "Q16")
      (value "BSS138")
      (footprint "eagle-import:SOT23")
      (libsource (lib "eagle-import") (part "BSS138"))
    )
    (comp (ref "R90")
      (value "499")
      (footprint "eagle-import:R0603")
      (libsource (lib "eagle-import") (part "R-EU_R0603"))
    )
    (comp (ref "R91")
      (value "499")
      (footprint "eagle-import:R0603")
      (libsource (lib "eagle-import") (part "R-EU_R0603"))
    )
    (comp (ref "R92")
      (value "10k")
      (footprint "eagle-import:R0603")
      (libsource (lib "eagle-import") (part "R-EU_R0603"))
    )
    (comp (ref "R93")
      (value "100")
      (footprint "eagle-import:R0603")
      (libsource (lib "eagle-import") (part "R-EU_R0603"))
    )
    (comp (ref "R94")
      (value "25m")
      (footprint "eagle-import:R1206")
      (libsource (lib "eagle-import") (part "R-EU_R1206"))
    )
    (comp (ref "R100")
      (value "499")
      (footprint "eagle-import:R0603")
      (libsource (lib "eagle-import") (part "R-EU_R0603"))
    )
    (comp (ref "R101")
      (value "499")
      (footprint "eagle-import:R0603")
      (libsource (lib "eagle-import") (part "R-EU_R0603"))
    )
    (comp (ref "R102")
      (value "10k")
      (footprint "eagle-import:R0603")
      (libsource (lib "eagle-import") (part "R-EU_R0603"))
    )
    (comp (ref "R103")
      (value "100")
      (footprint "eagle-import:R0603")
      (libsource (lib "eagle-import") (part "R-EU_R0603"))
    )
    (comp (ref "R104")
      (value "25m")
      (footprint "eagle-import:R1206")
      (libsource (lib "eagle-import") (part "R-EU_R1206"))
    )
    (comp (ref "RELAY15")
      (value "TLP241A(LF1,TP1)")
      (footprint "eagle-import:TP1_5")
      (libsource (lib "eagle-import") (part "TLP241A(?)LF1,TP1"))
    )
    (comp (ref "RELAY16")
      (value "TLP241A(LF1,TP1)")
      (footprint "eagle-import:TP1_5")
      (libsource (lib "eagle-import") (part "TLP241A(?)LF1,TP1"))
    )
    (comp (ref "X15")
      (value "AKL055-2")
      (footprint "eagle-import:AKL055-2")
      (libsource (lib "eagle-import") (part "AKL055-2"))
    )
    (comp (ref "X16")
      (value "AKL055-2")
      (footprint "eagle-import:AKL055-2")
      (libsource (lib "eagle-import") (part "AKL055-2"))
    )
    (comp (ref "C24")
      (value "100n")
      (footprint "eagle-import:C0603")
      (libsource (lib "eagle-import") (part "C-EUC0603"))
    )
    (comp (ref "C25")
      (value "100n")
      (footprint "eagle-import:C0603")
      (libsource (lib "eagle-import") (part "C-EUC0603"))
    )
    (comp (ref "D12")
      (value "60V, 2A")
      (footprint "eagle-import:SMB")
      (libsource (lib "eagle-import") (part "SCHOTTKY-DIODESMD"))
    )
    (comp (ref "D13")
      (value "60V, 2A")
      (footprint "eagle-import:SMB")
      (libsource (lib "eagle-import") (part "SCHOTTKY-DIODESMD"))
    )
    (comp (ref "LED15")
      (value "YELLOW")
      (footprint "eagle-import:CHIPLED_0805")
      (libsource (lib "eagle-import") (part "LEDCHIPLED_0805"))
    )
    (comp (ref "LED16")
      (value "YELLOW")
      (footprint "eagle-import:CHIPLED_0805")
      (libsource (lib "eagle-import") (part "LEDCHIPLED_0805"))
    )
    (comp (ref "MONITOR11")
      (value "INA226")
      (footprint "eagle-import:MSOP10")
      (libsource (lib "eagle-import") (part "INA226"))
    )
    (comp (ref "MONITOR12")
      (value "INA226")
      (footprint "eagle-import:MSOP10")
      (libsource (lib "eagle-import") (part "INA226"))
    )
    (comp (ref "Q11")
      (value "BSS138")
      (footprint "eagle-import:SOT23")
      (libsource (lib "eagle-import") (part "BSS138"))
    )
    (comp (ref "Q12")
      (value "BSS138")
      (footprint "eagle-import:SOT23")
      (libsource (lib "eagle-import") (part "BSS138"))
    )
    (comp (ref "R70")
      (value "499")
      (footprint "eagle-import:R0603")
      (libsource (lib "eagle-import") (part "R-EU_R0603"))
    )
    (comp (ref "R71")
      (value "499")
      (footprint "eagle-import:R0603")
      (libsource (lib "eagle-import") (part "R-EU_R0603"))
    )
    (comp (ref "R72")
      (value "10k")
      (footprint "eagle-import:R0603")
      (libsource (lib "eagle-import") (part "R-EU_R0603"))
    )
    (comp (ref "R73")
      (value "100")
      (footprint "eagle-import:R0603")
      (libsource (lib "eagle-import") (part "R-EU_R0603"))
    )
    (comp (ref "R74")
      (value "25m")
      (footprint "eagle-import:R1206")
      (libsource (lib "eagle-import") (part "R-EU_R1206"))
    )
    (comp (ref "R75")
      (value "499")
      (footprint "eagle-import:R0603")
      (libsource (lib "eagle-import") (part "R-EU_R0603"))
    )
    (comp (ref "R76")
      (value "499")
      (footprint "eagle-import:R0603")
      (libsource (lib "eagle-import") (part "R-EU_R0603"))
    )
    (comp (ref "R77")
      (value "10k")
      (footprint "eagle-import:R0603")
      (libsource (lib "eagle-import") (part "R-EU_R0603"))
    )
    (comp (ref "R78")
      (value "100")
      (footprint "eagle-import:R0603")
      (libsource (lib "eagle-import") (part "R-EU_R0603"))
    )
    (comp (ref "R79")
      (value "25m")
      (footprint "eagle-import:R1206")
      (libsource (lib "eagle-import") (part "R-EU_R1206"))
    )
    (comp (ref "RELAY11")
      (value "TLP241A(LF1,TP1)")
      (footprint "eagle-import:TP1_5")
      (libsource (lib "eagle-import") (part "TLP241A(?)LF1,TP1"))
    )
    (comp (ref "RELAY12")
      (value "TLP241A(LF1,TP1)")
      (footprint "eagle-import:TP1_5")
      (libsource (lib "eagle-import") (part "TLP241A(?)LF1,TP1"))
    )
    (comp (ref "X11")
      (value "AKL055-2")
      (footprint "eagle-import:AKL055-2")
      (libsource (lib "eagle-import") (part "AKL055-2"))
    )
    (comp (ref "X12")
      (value "AKL055-2")
      (footprint "eagle-import:AKL055-2")
      (libsource (lib "eagle-import") (part "AKL055-2"))
    )
    (comp (ref "C22")
      (value "100n")
      (footprint "eagle-import:C0603")
      (libsource (lib "eagle-import") (part "C-EUC0603"))
    )
    (comp (ref "C23")
      (value "100n")
      (footprint "eagle-import:C0603")
      (libsource (lib "eagle-import") (part "C-EUC0603"))
    )
    (comp (ref "D10")
      (value "60V, 2A")
      (footprint "eagle-import:SMB")
      (libsource (lib "eagle-import") (part "SCHOTTKY-DIODESMD"))
    )
    (comp (ref "D11")
      (value "60V, 2A")
      (footprint "eagle-import:SMB")
      (libsource (lib "eagle-import") (part "SCHOTTKY-DIODESMD"))
    )
    (comp (ref "LED13")
      (value "YELLOW")
      (footprint "eagle-import:CHIPLED_0805")
      (libsource (lib "eagle-import") (part "LEDCHIPLED_0805"))
    )
    (comp (ref "LED14")
      (value "YELLOW")
      (footprint "eagle-import:CHIPLED_0805")
      (libsource (lib "eagle-import") (part "LEDCHIPLED_0805"))
    )
    (comp (ref "MONITOR9")
      (value "INA226")
      (footprint "eagle-import:MSOP10")
      (libsource (lib "eagle-import") (part "INA226"))
    )
    (comp (ref "MONITOR10")
      (value "INA226")
      (footprint "eagle-import:MSOP10")
      (libsource (lib "eagle-import") (part "INA226"))
    )
    (comp (ref "Q9")
      (value "BSS138")
      (footprint "eagle-import:SOT23")
      (libsource (lib "eagle-import") (part "BSS138"))
    )
    (comp (ref "Q10")
      (value "BSS138")
      (footprint "eagle-import:SOT23")
      (libsource (lib "eagle-import") (part "BSS138"))
    )
    (comp (ref "R60")
      (value "499")
      (footprint "eagle-import:R0603")
      (libsource (lib "eagle-import") (part "R-EU_R0603"))
    )
    (comp (ref "R61")
      (value "499")
      (footprint "eagle-import:R0603")
      (libsource (lib "eagle-import") (part "R-EU_R0603"))
    )
    (comp (ref "R62")
      (value "10k")
      (footprint "eagle-import:R0603")
      (libsource (lib "eagle-import") (part "R-EU_R0603"))
    )
    (comp (ref "R63")
      (value "100")
      (footprint "eagle-import:R0603")
      (libsource (lib "eagle-import") (part "R-EU_R0603"))
    )
    (comp (ref "R64")
      (value "25m")
      (footprint "eagle-import:R1206")
      (libsource (lib "eagle-import") (part "R-EU_R1206"))
    )
    (comp (ref "R65")
      (value "499")
      (footprint "eagle-import:R0603")
      (libsource (lib "eagle-import") (part "R-EU_R0603"))
    )
    (comp (ref "R66")
      (value "499")
      (footprint "eagle-import:R0603")
      (libsource (lib "eagle-import") (part "R-EU_R0603"))
    )
    (comp (ref "R67")
      (value "10k")
      (footprint "eagle-import:R0603")
      (libsource (lib "eagle-import") (part "R-EU_R0603"))
    )
    (comp (ref "R68")
      (value "100")
      (footprint "eagle-import:R0603")
      (libsource (lib "eagle-import") (part "R-EU_R0603"))
    )
    (comp (ref "R69")
      (value "25m")
      (footprint "eagle-import:R1206")
      (libsource (lib "eagle-import") (part "R-EU_R1206"))
    )
    (comp (ref "RELAY9")
      (value "TLP241A(LF1,TP1)")
      (footprint "eagle-import:TP1_5")
      (libsource (lib "eagle-import") (part "TLP241A(?)LF1,TP1"))
    )
    (comp (ref "RELAY10")
      (value "TLP241A(LF1,TP1)")
      (footprint "eagle-import:TP1_5")
      (libsource (lib "eagle-import") (part "TLP241A(?)LF1,TP1"))
    )
    (comp (ref "X9")
      (value "AKL055-2")
      (footprint "eagle-import:AKL055-2")
      (libsource (lib "eagle-import") (part "AKL055-2"))
    )
    (comp (ref "X10")
      (value "AKL055-2")
      (footprint "eagle-import:AKL055-2")
      (libsource (lib "eagle-import") (part "AKL055-2"))
    )
    (comp (ref "C18")
      (value "100n")
      (footprint "eagle-import:C0603")
      (libsource (lib "eagle-import") (part "C-EUC0603"))
    )
    (comp (ref "C19")
      (value "100n")
      (footprint "eagle-import:C0603")
      (libsource (lib "eagle-import") (part "C-EUC0603"))
    )
    (comp (ref "D6")
      (value "60V, 2A")
      (footprint "eagle-import:SMB")
      (libsource (lib "eagle-import") (part "SCHOTTKY-DIODESMD"))
    )
    (comp (ref "D7")
      (value "60V, 2A")
      (footprint "eagle-import:SMB")
      (libsource (lib "eagle-import") (part "SCHOTTKY-DIODESMD"))
    )
    (comp (ref "LED9")
      (value "YELLOW")
      (footprint "eagle-import:CHIPLED_0805")
      (libsource (lib "eagle-import") (part "LEDCHIPLED_0805"))
    )
    (comp (ref "LED10")
      (value "YELLOW")
      (footprint "eagle-import:CHIPLED_0805")
      (libsource (lib "eagle-import") (part "LEDCHIPLED_0805"))
    )
    (comp (ref "MONITOR5")
      (value "INA226")
      (footprint "eagle-import:MSOP10")
      (libsource (lib "eagle-import") (part "INA226"))
    )
    (comp (ref "MONITOR6")
      (value "INA226")
      (footprint "eagle-import:MSOP10")
      (libsource (lib "eagle-import") (part "INA226"))
    )
    (comp (ref "Q5")
      (value "BSS138")
      (footprint "eagle-import:SOT23")
      (libsource (lib "eagle-import") (part "BSS138"))
    )
    (comp (ref "Q6")
      (value "BSS138")
      (footprint "eagle-import:SOT23")
      (libsource (lib "eagle-import") (part "BSS138"))
    )
    (comp (ref "R40")
      (value "499")
      (footprint "eagle-import:R0603")
      (libsource (lib "eagle-import") (part "R-EU_R0603"))
    )
    (comp (ref "R41")
      (value "499")
      (footprint "eagle-import:R0603")
      (libsource (lib "eagle-import") (part "R-EU_R0603"))
    )
    (comp (ref "R42")
      (value "10k")
      (footprint "eagle-import:R0603")
      (libsource (lib "eagle-import") (part "R-EU_R0603"))
    )
    (comp (ref "R43")
      (value "100")
      (footprint "eagle-import:R0603")
      (libsource (lib "eagle-import") (part "R-EU_R0603"))
    )
    (comp (ref "R44")
      (value "25m")
      (footprint "eagle-import:R1206")
      (libsource (lib "eagle-import") (part "R-EU_R1206"))
    )
    (comp (ref "R45")
      (value "499")
      (footprint "eagle-import:R0603")
      (libsource (lib "eagle-import") (part "R-EU_R0603"))
    )
    (comp (ref "R46")
      (value "499")
      (footprint "eagle-import:R0603")
      (libsource (lib "eagle-import") (part "R-EU_R0603"))
    )
    (comp (ref "R47")
      (value "10k")
      (footprint "eagle-import:R0603")
      (libsource (lib "eagle-import") (part "R-EU_R0603"))
    )
    (comp (ref "R48")
      (value "100")
      (footprint "eagle-import:R0603")
      (libsource (lib "eagle-import") (part "R-EU_R0603"))
    )
    (comp (ref "R49")
      (value "25m")
      (footprint "eagle-import:R1206")
      (libsource (lib "eagle-import") (part "R-EU_R1206"))
    )
    (comp (ref "RELAY5")
      (value "TLP241A(LF1,TP1)")
      (footprint "eagle-import:TP1_5")
      (libsource (lib "eagle-import") (part "TLP241A(?)LF1,TP1"))
    )
    (comp (ref "RELAY6")
      (value "TLP241A(LF1,TP1)")
      (footprint "eagle-import:TP1_5")
      (libsource (lib "eagle-import") (part "TLP241A(?)LF1,TP1"))
    )
    (comp (ref "X5")
      (value "AKL055-2")
      (footprint "eagle-import:AKL055-2")
      (libsource (lib "eagle-import") (part "AKL055-2"))
    )
    (comp (ref "X6")
      (value "AKL055-2")
      (footprint "eagle-import:AKL055-2")
      (libsource (lib "eagle-import") (part "AKL055-2"))
    )
    (comp (ref "C20")
      (value "100n")
      (footprint "eagle-import:C0603")
      (libsource (lib "eagle-import") (part "C-EUC0603"))
    )
    (comp (ref "C21")
      (value "100n")
      (footprint "eagle-import:C0603")
      (libsource (lib "eagle-import") (part "C-EUC0603"))
    )
    (comp (ref "D8")
      (value "60V, 2A")
      (footprint "eagle-import:SMB")
      (libsource (lib "eagle-import") (part "SCHOTTKY-DIODESMD"))
    )
    (comp (ref "D9")
      (value "60V, 2A")
      (footprint "eagle-import:SMB")
      (libsource (lib "eagle-import") (part "SCHOTTKY-DIODESMD"))
    )
    (comp (ref "LED11")
      (value "YELLOW")
      (footprint "eagle-import:CHIPLED_0805")
      (libsource (lib "eagle-import") (part "LEDCHIPLED_0805"))
    )
    (comp (ref "LED12")
      (value "YELLOW")
      (footprint "eagle-import:CHIPLED_0805")
      (libsource (lib "eagle-import") (part "LEDCHIPLED_0805"))
    )
    (comp (ref "MONITOR7")
      (value "INA226")
      (footprint "eagle-import:MSOP10")
      (libsource (lib "eagle-import") (part "INA226"))
    )
    (comp (ref "MONITOR8")
      (value "INA226")
      (footprint "eagle-import:MSOP10")
      (libsource (lib "eagle-import") (part "INA226"))
    )
    (comp (ref "Q7")
      (value "BSS138")
      (footprint "eagle-import:SOT23")
      (libsource (lib "eagle-import") (part "BSS138"))
    )
    (comp (ref "Q8")
      (value "BSS138")
      (footprint "eagle-import:SOT23")
      (libsource (lib "eagle-import") (part "BSS138"))
    )
    (comp (ref "R50")
      (value "499")
      (footprint "eagle-import:R0603")
      (libsource (lib "eagle-import") (part "R-EU_R0603"))
    )
    (comp (ref "R51")
      (value "499")
      (footprint "eagle-import:R0603")
      (libsource (lib "eagle-import") (part "R-EU_R0603"))
    )
    (comp (ref "R52")
      (value "10k")
      (footprint "eagle-import:R0603")
      (libsource (lib "eagle-import") (part "R-EU_R0603"))
    )
    (comp (ref "R53")
      (value "100")
      (footprint "eagle-import:R0603")
      (libsource (lib "eagle-import") (part "R-EU_R0603"))
    )
    (comp (ref "R54")
      (value "25m")
      (footprint "eagle-import:R1206")
      (libsource (lib "eagle-import") (part "R-EU_R1206"))
    )
    (comp (ref "R55")
      (value "499")
      (footprint "eagle-import:R0603")
      (libsource (lib "eagle-import") (part "R-EU_R0603"))
    )
    (comp (ref "R56")
      (value "499")
      (footprint "eagle-import:R0603")
      (libsource (lib "eagle-import") (part "R-EU_R0603"))
    )
    (comp (ref "R57")
      (value "10k")
      (footprint "eagle-import:R0603")
      (libsource (lib "eagle-import") (part "R-EU_R0603"))
    )
    (comp (ref "R58")
      (value "100")
      (footprint "eagle-import:R0603")
      (libsource (lib "eagle-import") (part "R-EU_R0603"))
    )
    (comp (ref "R59")
      (value "25m")
      (footprint "eagle-import:R1206")
      (libsource (lib "eagle-import") (part "R-EU_R1206"))
    )
    (comp (ref "RELAY7")
      (value "TLP241A(LF1,TP1)")
      (footprint "eagle-import:TP1_5")
      (libsource (lib "eagle-import") (part "TLP241A(?)LF1,TP1"))
    )
    (comp (ref "RELAY8")
      (value "TLP241A(LF1,TP1)")
      (footprint "eagle-import:TP1_5")
      (libsource (lib "eagle-import") (part "TLP241A(?)LF1,TP1"))
    )
    (comp (ref "X7")
      (value "AKL055-2")
      (footprint "eagle-import:AKL055-2")
      (libsource (lib "eagle-import") (part "AKL055-2"))
    )
    (comp (ref "X8")
      (value "AKL055-2")
      (footprint "eagle-import:AKL055-2")
      (libsource (lib "eagle-import") (part "AKL055-2"))
    )
  )
  (nets
    (net (code "1") (name "GND") (class "Default")
      (node (ref "C1") (pin "2") (pinfunction "2_2") (pintype "passive"))
      (node (ref "C10") (pin "2") (pinfunction "2_2") (pintype "passive"))
      (node (ref "C11") (pin "2") (pinfunction "2_2") (pintype "passive"))
      (node (ref "C12") (pin "2") (pinfunction "2_2") (pintype "passive"))
      (node (ref "C14") (pin "2") (pinfunction "2_2") (pintype "passive"))
      (node (ref "C2") (pin "2") (pinfunction "2_2") (pintype "passive"))
      (node (ref "C4") (pin "2") (pinfunction "2_2") (pintype "passive"))
      (node (ref "C5") (pin "2") (pinfunction "2_2") (pintype "passive"))
      (node (ref "C6") (pin "2") (pinfunction "2_2") (pintype "passive"))
      (node (ref "C7") (pin "2") (pinfunction "2_2") (pintype "passive"))
      (node (ref "C9") (pin "2") (pinfunction "2_2") (pintype "passive"))
      (node (ref "IC1") (pin "16") (pinfunction "VSS_16") (pintype "bidirectional"))
      (node (ref "IC1") (pin "32") (pinfunction "VSS_32") (pintype "bidirectional"))
      (node (ref "IC2") (pin "1") (pinfunction "GND_1") (pintype "power_in"))
      (node (ref "IC3") (pin "4") (pinfunction "GND1_4") (pintype "bidirectional"))
      (node (ref "IC4") (pin "3") (pinfunction "EMITTER_3") (pintype "passive"))
      (node (ref "J1") (pin "5") (pinfunction "5_5") (pintype "passive"))
      (node (ref "J2") (pin "3") (pinfunction "3_3") (pintype "passive"))
      (node (ref "J2") (pin "5") (pinfunction "5_5") (pintype "passive"))
      (node (ref "LED1") (pin "C2") (pinfunction "C_C2") (pintype "passive"))
      (node (ref "LED2") (pin "C") (pinfunction "C_C") (pintype "passive"))
      (node (ref "Q1") (pin "2") (pinfunction "S_2") (pintype "passive"))
      (node (ref "Q10") (pin "2") (pinfunction "S_2") (pintype "passive"))
      (node (ref "Q11") (pin "2") (pinfunction "S_2") (pintype "passive"))
      (node (ref "Q12") (pin "2") (pinfunction "S_2") (pintype "passive"))
      (node (ref "Q13") (pin "2") (pinfunction "S_2") (pintype "passive"))
      (node (ref "Q14") (pin "2") (pinfunction "S_2") (pintype "passive"))
      (node (ref "Q15") (pin "2") (pinfunction "S_2") (pintype "passive"))
      (node (ref "Q16") (pin "2") (pinfunction "S_2") (pintype "passive"))
      (node (ref "Q2") (pin "2") (pinfunction "S_2") (pintype "passive"))
      (node (ref "Q3") (pin "2") (pinfunction "S_2") (pintype "passive"))
      (node (ref "Q4") (pin "2") (pinfunction "S_2") (pintype "passive"))
      (node (ref "Q5") (pin "2") (pinfunction "S_2") (pintype "passive"))
      (node (ref "Q6") (pin "2") (pinfunction "S_2") (pintype "passive"))
      (node (ref "Q7") (pin "2") (pinfunction "S_2") (pintype "passive"))
      (node (ref "Q8") (pin "2") (pinfunction "S_2") (pintype "passive"))
      (node (ref "Q9") (pin "2") (pinfunction "S_2") (pintype "passive"))
      (node (ref "R1") (pin "1") (pinfunction "1_1") (pintype "passive"))
      (node (ref "R102") (pin "1") (pinfunction "1_1") (pintype "passive"))
      (node (ref "R16") (pin "1") (pinfunction "1_1") (pintype "passive"))
      (node (ref "R2") (pin "1") (pinfunction "1_1") (pintype "passive"))
      (node (ref "R27") (pin "1") (pinfunction "1_1") (pintype "passive"))
      (node (ref "R32") (pin "1") (pinfunction "1_1") (pintype "passive"))
      (node (ref "R37") (pin "1") (pinfunction "1_1") (pintype "passive"))
      (node (ref "R42") (pin "1") (pinfunction "1_1") (pintype "passive"))
      (node (ref "R47") (pin "1") (pinfunction "1_1") (pintype "passive"))
      (node (ref "R52") (pin "1") (pinfunction "1_1") (pintype "passive"))
      (node (ref "R57") (pin "1") (pinfunction "1_1") (pintype "passive"))
      (node (ref "R62") (pin "1") (pinfunction "1_1") (pintype "passive"))
      (node (ref "R67") (pin "1") (pinfunction "1_1") (pintype "passive"))
      (node (ref "R72") (pin "1") (pinfunction "1_1") (pintype "passive"))
      (node (ref "R77") (pin "1") (pinfunction "1_1") (pintype "passive"))
      (node (ref "R82") (pin "1") (pinfunction "1_1") (pintype "passive"))
      (node (ref "R87") (pin "1") (pinfunction "1_1") (pintype "passive"))
      (node (ref "R92") (pin "1") (pinfunction "1_1") (pintype "passive"))
      (node (ref "TP1") (pin "TP") (pinfunction "TP_TP") (pintype "input"))
      (node (ref "TP2") (pin "TP") (pinfunction "TP_TP") (pintype "input"))
      (node (ref "U1") (pin "2") (pinfunction "2_2") (pintype "power_in"))
      (node (ref "U2") (pin "2") (pinfunction "GND_2") (pintype "bidirectional"))
    )
    (net (code "2") (name "GNDISO") (class "Default")
      (node (ref "C13") (pin "2") (pinfunction "2_2") (pintype "passive"))
      (node (ref "C15") (pin "2") (pinfunction "2_2") (pintype "passive"))
      (node (ref "C16") (pin "2") (pinfunction "2_2") (pintype "passive"))
      (node (ref "C17") (pin "2") (pinfunction "2_2") (pintype "passive"))
      (node (ref "C18") (pin "2") (pinfunction "2_2") (pintype "passive"))
      (node (ref "C19") (pin "2") (pinfunction "2_2") (pintype "passive"))
      (node (ref "C20") (pin "2") (pinfunction "2_2") (pintype "passive"))
      (node (ref "C21") (pin "2") (pinfunction "2_2") (pintype "passive"))
      (node (ref "C22") (pin "2") (pinfunction "2_2") (pintype "passive"))
      (node (ref "C23") (pin "2") (pinfunction "2_2") (pintype "passive"))
      (node (ref "C24") (pin "2") (pinfunction "2_2") (pintype "passive"))
      (node (ref "C25") (pin "2") (pinfunction "2_2") (pintype "passive"))
      (node (ref "C26") (pin "2") (pinfunction "2_2") (pintype "passive"))
      (node (ref "C27") (pin "2") (pinfunction "2_2") (pintype "passive"))
      (node (ref "C28") (pin "2") (pinfunction "2_2") (pintype "passive"))
      (node (ref "C3") (pin "2") (pinfunction "2_2") (pintype "passive"))
      (node (ref "C30") (pin "2") (pinfunction "2_2") (pintype "passive"))
      (node (ref "C8") (pin "2") (pinfunction "2_2") (pintype "passive"))
      (node (ref "D1") (pin "A") (pinfunction "A_A") (pintype "passive"))
      (node (ref "D10") (pin "A") (pinfunction "A_A") (pintype "passive"))
      (node (ref "D11") (pin "A") (pinfunction "A_A") (pintype "passive"))
      (node (ref "D12") (pin "A") (pinfunction "A_A") (pintype "passive"))
      (node (ref "D13") (pin "A") (pinfunction "A_A") (pintype "passive"))
      (node (ref "D14") (pin "A") (pinfunction "A_A") (pintype "passive"))
      (node (ref "D15") (pin "A") (pinfunction "A_A") (pintype "passive"))
      (node (ref "D16") (pin "A") (pinfunction "A_A") (pintype "passive"))
      (node (ref "D18") (pin "A") (pinfunction "A_A") (pintype "passive"))
      (node (ref "D3") (pin "A") (pinfunction "A_A") (pintype "passive"))
      (node (ref "D4") (pin "A") (pinfunction "A_A") (pintype "passive"))
      (node (ref "D5") (pin "A") (pinfunction "A_A") (pintype "passive"))
      (node (ref "D6") (pin "A") (pinfunction "A_A") (pintype "passive"))
      (node (ref "D7") (pin "A") (pinfunction "A_A") (pintype "passive"))
      (node (ref "D8") (pin "A") (pinfunction "A_A") (pintype "passive"))
      (node (ref "D9") (pin "A") (pinfunction "A_A") (pintype "passive"))
      (node (ref "IC2") (pin "4") (pinfunction "0V_4") (pintype "power_in"))
      (node (ref "IC3") (pin "5") (pinfunction "GND2_5") (pintype "bidirectional"))
      (node (ref "LED3") (pin "C") (pinfunction "C_C") (pintype "passive"))
      (node (ref "MONITOR1") (pin "1") (pinfunction "A1_1") (pintype "input"))
      (node (ref "MONITOR1") (pin "2") (pinfunction "A0_2") (pintype "input"))
      (node (ref "MONITOR1") (pin "7") (pinfunction "GND_7") (pintype "power_in"))
      (node (ref "MONITOR10") (pin "7") (pinfunction "GND_7") (pintype "power_in"))
      (node (ref "MONITOR11") (pin "7") (pinfunction "GND_7") (pintype "power_in"))
      (node (ref "MONITOR12") (pin "7") (pinfunction "GND_7") (pintype "power_in"))
      (node (ref "MONITOR13") (pin "2") (pinfunction "A0_2") (pintype "input"))
      (node (ref "MONITOR13") (pin "7") (pinfunction "GND_7") (pintype "power_in"))
      (node (ref "MONITOR14") (pin "7") (pinfunction "GND_7") (pintype "power_in"))
      (node (ref "MONITOR15") (pin "7") (pinfunction "GND_7") (pintype "power_in"))
      (node (ref "MONITOR16") (pin "7") (pinfunction "GND_7") (pintype "power_in"))
      (node (ref "MONITOR2") (pin "1") (pinfunction "A1_1") (pintype "input"))
      (node (ref "MONITOR2") (pin "7") (pinfunction "GND_7") (pintype "power_in"))
      (node (ref "MONITOR3") (pin "1") (pinfunction "A1_1") (pintype "input"))
      (node (ref "MONITOR3") (pin "7") (pinfunction "GND_7") (pintype "power_in"))
      (node (ref "MONITOR4") (pin "1") (pinfunction "A1_1") (pintype "input"))
      (node (ref "MONITOR4") (pin "7") (pinfunction "GND_7") (pintype "power_in"))
      (node (ref "MONITOR5") (pin "2") (pinfunction "A0_2") (pintype "input"))
      (node (ref "MONITOR5") (pin "7") (pinfunction "GND_7") (pintype "power_in"))
      (node (ref "MONITOR6") (pin "7") (pinfunction "GND_7") (pintype "power_in"))
      (node (ref "MONITOR7") (pin "7") (pinfunction "GND_7") (pintype "power_in"))
      (node (ref "MONITOR8") (pin "7") (pinfunction "GND_7") (pintype "power_in"))
      (node (ref "MONITOR9") (pin "2") (pinfunction "A0_2") (pintype "input"))
      (node (ref "MONITOR9") (pin "7") (pinfunction "GND_7") (pintype "power_in"))
      (node (ref "R9") (pin "2") (pinfunction "2_2") (pintype "passive"))
      (node (ref "TP3") (pin "TP") (pinfunction "TP_TP") (pintype "input"))
      (node (ref "TP4") (pin "TP") (pinfunction "TP_TP") (pintype "input"))
      (node (ref "X17") (pin "1") (pinfunction "1_1") (pintype "passive"))
      (node (ref "X17") (pin "2") (pinfunction "2_2") (pintype "passive"))
      (node (ref "X17") (pin "3") (pinfunction "3_3") (pintype "passive"))
      (node (ref "X17") (pin "4") (pinfunction "4_4") (pintype "passive"))
    )
    (net (code "3") (name "LOAD1") (class "Default")
      (node (ref "D1") (pin "C") (pinfunction "C_C") (pintype "passive"))
      (node (ref "MONITOR1") (pin "8") (pinfunction "VBUS_8") (pintype "input"))
      (node (ref "MONITOR1") (pin "9") (pinfunction "IN-_9") (pintype "input"))
      (node (ref "R18") (pin "1") (pinfunction "1_1") (pintype "passive"))
      (node (ref "X1") (pin "1") (pinfunction "1_1") (pintype "passive"))
    )
    (net (code "4") (name "LOAD2") (class "Default")
      (node (ref "D3") (pin "C") (pinfunction "C_C") (pintype "passive"))
      (node (ref "MONITOR2") (pin "8") (pinfunction "VBUS_8") (pintype "input"))
      (node (ref "MONITOR2") (pin "9") (pinfunction "IN-_9") (pintype "input"))
      (node (ref "R29") (pin "1") (pinfunction "1_1") (pintype "passive"))
      (node (ref "X2") (pin "1") (pinfunction "1_1") (pintype "passive"))
    )
    (net (code "5") (name "LOAD3") (class "Default")
      (node (ref "D5") (pin "C") (pinfunction "C_C") (pintype "passive"))
      (node (ref "MONITOR3") (pin "8") (pinfunction "VBUS_8") (pintype "input"))
      (node (ref "MONITOR3") (pin "9") (pinfunction "IN-_9") (pintype "input"))
      (node (ref "R39") (pin "1") (pinfunction "1_1") (pintype "passive"))
      (node (ref "X3") (pin "1") (pinfunction "1_1") (pintype "passive"))
    )
    (net (code "6") (name "LOAD4") (class "Default")
      (node (ref "D4") (pin "C") (pinfunction "C_C") (pintype "passive"))
      (node (ref "MONITOR4") (pin "8") (pinfunction "VBUS_8") (pintype "input"))
      (node (ref "MONITOR4") (pin "9") (pinfunction "IN-_9") (pintype "input"))
      (node (ref "R34") (pin "1") (pinfunction "1_1") (pintype "passive"))
      (node (ref "X4") (pin "1") (pinfunction "1_1") (pintype "passive"))
    )
    (net (code "7") (name "LOAD5") (class "Default")
      (node (ref "D6") (pin "C") (pinfunction "C_C") (pintype "passive"))
      (node (ref "MONITOR5") (pin "8") (pinfunction "VBUS_8") (pintype "input"))
      (node (ref "MONITOR5") (pin "9") (pinfunction "IN-_9") (pintype "input"))
      (node (ref "R44") (pin "1") (pinfunction "1_1") (pintype "passive"))
      (node (ref "X5") (pin "1") (pinfunction "1_1") (pintype "passive"))
    )
    (net (code "8") (name "LOAD6") (class "Default")
      (node (ref "D7") (pin "C") (pinfunction "C_C") (pintype "passive"))
      (node (ref "MONITOR6") (pin "8") (pinfunction "VBUS_8") (pintype "input"))
      (node (ref "MONITOR6") (pin "9") (pinfunction "IN-_9") (pintype "input"))
      (node (ref "R49") (pin "1") (pinfunction "1_1") (pintype "passive"))
      (node (ref "X6") (pin "1") (pinfunction "1_1") (pintype "passive"))
    )
    (net (code "9") (name "LOAD7") (class "Default")
      (node (ref "D8") (pin "C") (pinfunction "C_C") (pintype "passive"))
      (node (ref "MONITOR7") (pin "8") (pinfunction "VBUS_8") (pintype "input"))
      (node (ref "MONITOR7") (pin "9") (pinfunction "IN-_9") (pintype "input"))
      (node (ref "R54") (pin "1") (pinfunction "1_1") (pintype "passive"))
      (node (ref "X7") (pin "1") (pinfunction "1_1") (pintype "passive"))
    )
    (net (code "10") (name "LOAD8") (class "Default")
      (node (ref "D9") (pin "C") (pinfunction "C_C") (pintype "passive"))
      (node (ref "MONITOR8") (pin "8") (pinfunction "VBUS_8") (pintype "input"))
      (node (ref "MONITOR8") (pin "9") (pinfunction "IN-_9") (pintype "input"))
      (node (ref "R59") (pin "1") (pinfunction "1_1") (pintype "passive"))
      (node (ref "X8") (pin "1") (pinfunction "1_1") (pintype "passive"))
    )
    (net (code "11") (name "LOAD9") (class "Default")
      (node (ref "D10") (pin "C") (pinfunction "C_C") (pintype "passive"))
      (node (ref "MONITOR9") (pin "8") (pinfunction "VBUS_8") (pintype "input"))
      (node (ref "MONITOR9") (pin "9") (pinfunction "IN-_9") (pintype "input"))
      (node (ref "R64") (pin "1") (pinfunction "1_1") (pintype "passive"))
      (node (ref "X9") (pin "1") (pinfunction "1_1") (pintype "passive"))
    )
    (net (code "12") (name "LOAD10") (class "Default")
      (node (ref "D11") (pin "C") (pinfunction "C_C") (pintype "passive"))
      (node (ref "MONITOR10") (pin "8") (pinfunction "VBUS_8") (pintype "input"))
      (node (ref "MONITOR10") (pin "9") (pinfunction "IN-_9") (pintype "input"))
      (node (ref "R69") (pin "1") (pinfunction "1_1") (pintype "passive"))
      (node (ref "X10") (pin "1") (pinfunction "1_1") (pintype "passive"))
    )
    (net (code "13") (name "LOAD11") (class "Default")
      (node (ref "D13") (pin "C") (pinfunction "C_C") (pintype "passive"))
      (node (ref "MONITOR11") (pin "8") (pinfunction "VBUS_8") (pintype "input"))
      (node (ref "MONITOR11") (pin "9") (pinfunction "IN-_9") (pintype "input"))
      (node (ref "R79") (pin "1") (pinfunction "1_1") (pintype "passive"))
      (node (ref "X11") (pin "1") (pinfunction "1_1") (pintype "passive"))
    )
    (net (code "14") (name "LOAD12") (class "Default")
      (node (ref "D12") (pin "C") (pinfunction "C_C") (pintype "passive"))
      (node (ref "MONITOR12") (pin "8") (pinfunction "VBUS_8") (pintype "input"))
      (node (ref "MONITOR12") (pin "9") (pinfunction "IN-_9") (pintype "input"))
      (node (ref "R74") (pin "1") (pinfunction "1_1") (pintype "passive"))
      (node (ref "X12") (pin "1") (pinfunction "1_1") (pintype "passive"))
    )
    (net (code "15") (name "LOAD13") (class "Default")
      (node (ref "D14") (pin "C") (pinfunction "C_C") (pintype "passive"))
      (node (ref "MONITOR13") (pin "8") (pinfunction "VBUS_8") (pintype "input"))
      (node (ref "MONITOR13") (pin "9") (pinfunction "IN-_9") (pintype "input"))
      (node (ref "R84") (pin "1") (pinfunction "1_1") (pintype "passive"))
      (node (ref "X13") (pin "1") (pinfunction "1_1") (pintype "passive"))
    )
    (net (code "16") (name "LOAD14") (class "Default")
      (node (ref "D15") (pin "C") (pinfunction "C_C") (pintype "passive"))
      (node (ref "MONITOR14") (pin "8") (pinfunction "VBUS_8") (pintype "input"))
      (node (ref "MONITOR14") (pin "9") (pinfunction "IN-_9") (pintype "input"))
      (node (ref "R89") (pin "1") (pinfunction "1_1") (pintype "passive"))
      (node (ref "X14") (pin "1") (pinfunction "1_1") (pintype "passive"))
    )
    (net (code "17") (name "LOAD15") (class "Default")
      (node (ref "D16") (pin "C") (pinfunction "C_C") (pintype "passive"))
      (node (ref "MONITOR15") (pin "8") (pinfunction "VBUS_8") (pintype "input"))
      (node (ref "MONITOR15") (pin "9") (pinfunction "IN-_9") (pintype "input"))
      (node (ref "R94") (pin "1") (pinfunction "1_1") (pintype "passive"))
      (node (ref "X15") (pin "1") (pinfunction "1_1") (pintype "passive"))
    )
    (net (code "18") (name "LOAD16") (class "Default")
      (node (ref "D18") (pin "C") (pinfunction "C_C") (pintype "passive"))
      (node (ref "MONITOR16") (pin "8") (pinfunction "VBUS_8") (pintype "input"))
      (node (ref "MONITOR16") (pin "9") (pinfunction "IN-_9") (pintype "input"))
      (node (ref "R104") (pin "1") (pinfunction "1_1") (pintype "passive"))
      (node (ref "X16") (pin "1") (pinfunction "1_1") (pintype "passive"))
    )
    (net (code "19") (name "Net-(F2-Pad2)") (class "Default")
      (node (ref "F2") (pin "2") (pinfunction "2_2") (pintype "passive"))
      (node (ref "S1") (pin "2") (pinfunction "2_2") (pintype "passive"))
    )
    (net (code "20") (name "Net-(IC1-BOOT0-PH3)") (class "Default")
      (node (ref "IC1") (pin "31") (pinfunction "BOOT0-PH3_31") (pintype "bidirectional"))
      (node (ref "R1") (pin "2") (pinfunction "2_2") (pintype "passive"))
    )
    (net (code "21") (name "Net-(IC2-+VO)") (class "Default")
      (node (ref "F1") (pin "1") (pinfunction "1_1") (pintype "passive"))
      (node (ref "IC2") (pin "5") (pinfunction "+VO_5") (pintype "power_in"))
    )
    (net (code "22") (name "Net-(IC4-ANODE)") (class "Default")
      (node (ref "IC4") (pin "1") (pinfunction "ANODE_1") (pintype "passive"))
      (node (ref "R7") (pin "1") (pinfunction "1_1") (pintype "passive"))
    )
    (net (code "23") (name "Net-(J1-Pad1)") (class "Default")
      (node (ref "J1") (pin "1") (pinfunction "1_1") (pintype "passive"))
      (node (ref "S1") (pin "3") (pinfunction "3_3") (pintype "passive"))
      (node (ref "U1") (pin "5") (pinfunction "5_5") (pintype "power_in"))
    )
    (net (code "24") (name "Net-(J1-Pad2)") (class "Default")
      (node (ref "J1") (pin "2") (pinfunction "2_2") (pintype "passive"))
      (node (ref "U1") (pin "1") (pinfunction "1_1") (pintype "bidirectional"))
    )
    (net (code "25") (name "Net-(J1-Pad3)") (class "Default")
      (node (ref "J1") (pin "3") (pinfunction "3_3") (pintype "passive"))
      (node (ref "U1") (pin "3") (pinfunction "3_3") (pintype "bidirectional"))
    )
    (net (code "26") (name "Net-(J1-SHIELD-PadSH1)") (class "Default")
      (node (ref "J1") (pin "SH1") (pinfunction "SHIELD_SH1") (pintype "passive"))
      (node (ref "J1") (pin "SH2") (pinfunction "SHIELD_SH2") (pintype "passive"))
      (node (ref "J1") (pin "SH3") (pinfunction "SHIELD_SH3") (pintype "passive"))
      (node (ref "J1") (pin "SH4") (pinfunction "SHIELD_SH4") (pintype "passive"))
      (node (ref "J1") (pin "SH5") (pinfunction "SHIELD_SH5") (pintype "passive"))
      (node (ref "J1") (pin "SH6") (pinfunction "SHIELD_SH6") (pintype "passive"))
      (node (ref "R2") (pin "2") (pinfunction "2_2") (pintype "passive"))
    )
    (net (code "27") (name "Net-(LED1A-A)") (class "Default")
      (node (ref "LED1") (pin "A2") (pinfunction "A_A2") (pintype "passive"))
      (node (ref "R13") (pin "1") (pinfunction "1_1") (pintype "passive"))
    )
    (net (code "28") (name "Net-(LED1B-A)") (class "Default")
      (node (ref "LED1") (pin "A1") (pinfunction "A_A1") (pintype "passive"))
      (node (ref "R12") (pin "1") (pinfunction "1_1") (pintype "passive"))
    )
    (net (code "29") (name "Net-(LED2-PadA)") (class "Default")
      (node (ref "LED2") (pin "A") (pinfunction "A_A") (pintype "passive"))
      (node (ref "R11") (pin "1") (pinfunction "1_1") (pintype "passive"))
    )
    (net (code "30") (name "Net-(LED3-PadA)") (class "Default")
      (node (ref "LED3") (pin "A") (pinfunction "A_A") (pintype "passive"))
      (node (ref "R10") (pin "1") (pinfunction "1_1") (pintype "passive"))
    )
    (net (code "31") (name "Net-(LED4-PadA)") (class "Default")
      (node (ref "LED4") (pin "A") (pinfunction "A_A") (pintype "passive"))
      (node (ref "R14") (pin "1") (pinfunction "1_1") (pintype "passive"))
    )
    (net (code "32") (name "Net-(LED6-PadA)") (class "Default")
      (node (ref "LED6") (pin "A") (pinfunction "A_A") (pintype "passive"))
      (node (ref "R25") (pin "1") (pinfunction "1_1") (pintype "passive"))
    )
    (net (code "33") (name "Net-(LED7-PadA)") (class "Default")
      (node (ref "LED7") (pin "A") (pinfunction "A_A") (pintype "passive"))
      (node (ref "R30") (pin "1") (pinfunction "1_1") (pintype "passive"))
    )
    (net (code "34") (name "Net-(LED8-PadA)") (class "Default")
      (node (ref "LED8") (pin "A") (pinfunction "A_A") (pintype "passive"))
      (node (ref "R35") (pin "1") (pinfunction "1_1") (pintype "passive"))
    )
    (net (code "35") (name "Net-(LED9-PadA)") (class "Default")
      (node (ref "LED9") (pin "A") (pinfunction "A_A") (pintype "passive"))
      (node (ref "R40") (pin "1") (pinfunction "1_1") (pintype "passive"))
    )
    (net (code "36") (name "Net-(LED10-PadA)") (class "Default")
      (node (ref "LED10") (pin "A") (pinfunction "A_A") (pintype "passive"))
      (node (ref "R45") (pin "1") (pinfunction "1_1") (pintype "passive"))
    )
    (net (code "37") (name "Net-(LED11-PadA)") (class "Default")
      (node (ref "LED11") (pin "A") (pinfunction "A_A") (pintype "passive"))
      (node (ref "R50") (pin "1") (pinfunction "1_1") (pintype "passive"))
    )
    (net (code "38") (name "Net-(LED12-PadA)") (class "Default")
      (node (ref "LED12") (pin "A") (pinfunction "A_A") (pintype "passive"))
      (node (ref "R55") (pin "1") (pinfunction "1_1") (pintype "passive"))
    )
    (net (code "39") (name "Net-(LED13-PadA)") (class "Default")
      (node (ref "LED13") (pin "A") (pinfunction "A_A") (pintype "passive"))
      (node (ref "R60") (pin "1") (pinfunction "1_1") (pintype "passive"))
    )
    (net (code "40") (name "Net-(LED14-PadA)") (class "Default")
      (node (ref "LED14") (pin "A") (pinfunction "A_A") (pintype "passive"))
      (node (ref "R65") (pin "1") (pinfunction "1_1") (pintype "passive"))
    )
    (net (code "41") (name "Net-(LED15-PadA)") (class "Default")
      (node (ref "LED15") (pin "A") (pinfunction "A_A") (pintype "passive"))
      (node (ref "R70") (pin "1") (pinfunction "1_1") (pintype "passive"))
    )
    (net (code "42") (name "Net-(LED16-PadA)") (class "Default")
      (node (ref "LED16") (pin "A") (pinfunction "A_A") (pintype "passive"))
      (node (ref "R75") (pin "1") (pinfunction "1_1") (pintype "passive"))
    )
    (net (code "43") (name "Net-(LED17-PadA)") (class "Default")
      (node (ref "LED17") (pin "A") (pinfunction "A_A") (pintype "passive"))
      (node (ref "R80") (pin "1") (pinfunction "1_1") (pintype "passive"))
    )
    (net (code "44") (name "Net-(LED18-PadA)") (class "Default")
      (node (ref "LED18") (pin "A") (pinfunction "A_A") (pintype "passive"))
      (node (ref "R85") (pin "1") (pinfunction "1_1") (pintype "passive"))
    )
    (net (code "45") (name "Net-(LED19-PadA)") (class "Default")
      (node (ref "LED19") (pin "A") (pinfunction "A_A") (pintype "passive"))
      (node (ref "R90") (pin "1") (pinfunction "1_1") (pintype "passive"))
    )
    (net (code "46") (name "Net-(LED21-PadA)") (class "Default")
      (node (ref "LED21") (pin "A") (pinfunction "A_A") (pintype "passive"))
      (node (ref "R100") (pin "1") (pinfunction "1_1") (pintype "passive"))
    )
    (net (code "47") (name "Net-(MONITOR1-IN+)") (class "Default")
      (node (ref "MONITOR1") (pin "10") (pinfunction "IN+_10") (pintype "input"))
      (node (ref "R18") (pin "2") (pinfunction "2_2") (pintype "passive"))
      (node (ref "RELAY1") (pin "P$3") (pinfunction "DRAIN1_P$3") (pintype "passive"))
    )
    (net (code "48") (name "Net-(MONITOR2-IN+)") (class "Default")
      (node (ref "MONITOR2") (pin "10") (pinfunction "IN+_10") (pintype "input"))
      (node (ref "R29") (pin "2") (pinfunction "2_2") (pintype "passive"))
      (node (ref "RELAY2") (pin "P$3") (pinfunction "DRAIN1_P$3") (pintype "passive"))
    )
    (net (code "49") (name "Net-(MONITOR3-IN+)") (class "Default")
      (node (ref "MONITOR3") (pin "10") (pinfunction "IN+_10") (pintype "input"))
      (node (ref "R39") (pin "2") (pinfunction "2_2") (pintype "passive"))
      (node (ref "RELAY3") (pin "P$3") (pinfunction "DRAIN1_P$3") (pintype "passive"))
    )
    (net (code "50") (name "Net-(MONITOR4-IN+)") (class "Default")
      (node (ref "MONITOR4") (pin "10") (pinfunction "IN+_10") (pintype "input"))
      (node (ref "R34") (pin "2") (pinfunction "2_2") (pintype "passive"))
      (node (ref "RELAY4") (pin "P$3") (pinfunction "DRAIN1_P$3") (pintype "passive"))
    )
    (net (code "51") (name "Net-(MONITOR5-IN+)") (class "Default")
      (node (ref "MONITOR5") (pin "10") (pinfunction "IN+_10") (pintype "input"))
      (node (ref "R44") (pin "2") (pinfunction "2_2") (pintype "passive"))
      (node (ref "RELAY5") (pin "P$3") (pinfunction "DRAIN1_P$3") (pintype "passive"))
    )
    (net (code "52") (name "Net-(MONITOR6-IN+)") (class "Default")
      (node (ref "MONITOR6") (pin "10") (pinfunction "IN+_10") (pintype "input"))
      (node (ref "R49") (pin "2") (pinfunction "2_2") (pintype "passive"))
      (node (ref "RELAY6") (pin "P$3") (pinfunction "DRAIN1_P$3") (pintype "passive"))
    )
    (net (code "53") (name "Net-(MONITOR7-IN+)") (class "Default")
      (node (ref "MONITOR7") (pin "10") (pinfunction "IN+_10") (pintype "input"))
      (node (ref "R54") (pin "2") (pinfunction "2_2") (pintype "passive"))
      (node (ref "RELAY7") (pin "P$3") (pinfunction "DRAIN1_P$3") (pintype "passive"))
    )
    (net (code "54") (name "Net-(MONITOR8-IN+)") (class "Default")
      (node (ref "MONITOR8") (pin "10") (pinfunction "IN+_10") (pintype "input"))
      (node (ref "R59") (pin "2") (pinfunction "2_2") (pintype "passive"))
      (node (ref "RELAY8") (pin "P$3") (pinfunction "DRAIN1_P$3") (pintype "passive"))
    )
    (net (code "55") (name "Net-(MONITOR9-IN+)") (class "Default")
      (node (ref "MONITOR9") (pin "10") (pinfunction "IN+_10") (pintype "input"))
      (node (ref "R64") (pin "2") (pinfunction "2_2") (pintype "passive"))
      (node (ref "RELAY9") (pin "P$3") (pinfunction "DRAIN1_P$3") (pintype "passive"))
    )
    (net (code "56") (name "Net-(MONITOR10-IN+)") (class "Default")
      (node (ref "MONITOR10") (pin "10") (pinfunction "IN+_10") (pintype "input"))
      (node (ref "R69") (pin "2") (pinfunction "2_2") (pintype "passive"))
      (node (ref "RELAY10") (pin "P$3") (pinfunction "DRAIN1_P$3") (pintype "passive"))
    )
    (net (code "57") (name "Net-(MONITOR11-IN+)") (class "Default")
      (node (ref "MONITOR11") (pin "10") (pinfunction "IN+_10") (pintype "input"))
      (node (ref "R79") (pin "2") (pinfunction "2_2") (pintype "passive"))
      (node (ref "RELAY11") (pin "P$3") (pinfunction "DRAIN1_P$3") (pintype "passive"))
    )
    (net (code "58") (name "Net-(MONITOR12-IN+)") (class "Default")
      (node (ref "MONITOR12") (pin "10") (pinfunction "IN+_10") (pintype "input"))
      (node (ref "R74") (pin "2") (pinfunction "2_2") (pintype "passive"))
      (node (ref "RELAY12") (pin "P$3") (pinfunction "DRAIN1_P$3") (pintype "passive"))
    )
    (net (code "59") (name "Net-(MONITOR13-IN+)") (class "Default")
      (node (ref "MONITOR13") (pin "10") (pinfunction "IN+_10") (pintype "input"))
      (node (ref "R84") (pin "2") (pinfunction "2_2") (pintype "passive"))
      (node (ref "RELAY13") (pin "P$3") (pinfunction "DRAIN1_P$3") (pintype "passive"))
    )
    (net (code "60") (name "Net-(MONITOR14-IN+)") (class "Default")
      (node (ref "MONITOR14") (pin "10") (pinfunction "IN+_10") (pintype "input"))
      (node (ref "R89") (pin "2") (pinfunction "2_2") (pintype "passive"))
      (node (ref "RELAY14") (pin "P$3") (pinfunction "DRAIN1_P$3") (pintype "passive"))
    )
    (net (code "61") (name "Net-(MONITOR15-IN+)") (class "Default")
      (node (ref "MONITOR15") (pin "10") (pinfunction "IN+_10") (pintype "input"))
      (node (ref "R94") (pin "2") (pinfunction "2_2") (pintype "passive"))
      (node (ref "RELAY15") (pin "P$3") (pinfunction "DRAIN1_P$3") (pintype "passive"))
    )
    (net (code "62") (name "Net-(MONITOR16-IN+)") (class "Default")
      (node (ref "MONITOR16") (pin "10") (pinfunction "IN+_10") (pintype "input"))
      (node (ref "R104") (pin "2") (pinfunction "2_2") (pintype "passive"))
      (node (ref "RELAY16") (pin "P$3") (pinfunction "DRAIN1_P$3") (pintype "passive"))
    )
    (net (code "63") (name "Net-(Q1-D)") (class "Default")
      (node (ref "LED4") (pin "C") (pinfunction "C_C") (pintype "passive"))
      (node (ref "Q1") (pin "3") (pinfunction "D_3") (pintype "passive"))
      (node (ref "RELAY1") (pin "P$2") (pinfunction "CATHODE_P$2") (pintype "passive"))
    )
    (net (code "64") (name "Net-(Q1-G)") (class "Default")
      (node (ref "Q1") (pin "1") (pinfunction "G_1") (pintype "passive"))
      (node (ref "R16") (pin "2") (pinfunction "2_2") (pintype "passive"))
      (node (ref "R17") (pin "1") (pinfunction "1_1") (pintype "passive"))
    )
    (net (code "65") (name "Net-(Q2-D)") (class "Default")
      (node (ref "LED6") (pin "C") (pinfunction "C_C") (pintype "passive"))
      (node (ref "Q2") (pin "3") (pinfunction "D_3") (pintype "passive"))
      (node (ref "RELAY2") (pin "P$2") (pinfunction "CATHODE_P$2") (pintype "passive"))
    )
    (net (code "66") (name "Net-(Q2-G)") (class "Default")
      (node (ref "Q2") (pin "1") (pinfunction "G_1") (pintype "passive"))
      (node (ref "R27") (pin "2") (pinfunction "2_2") (pintype "passive"))
      (node (ref "R28") (pin "1") (pinfunction "1_1") (pintype "passive"))
    )
    (net (code "67") (name "Net-(Q3-D)") (class "Default")
      (node (ref "LED8") (pin "C") (pinfunction "C_C") (pintype "passive"))
      (node (ref "Q3") (pin "3") (pinfunction "D_3") (pintype "passive"))
      (node (ref "RELAY3") (pin "P$2") (pinfunction "CATHODE_P$2") (pintype "passive"))
    )
    (net (code "68") (name "Net-(Q3-G)") (class "Default")
      (node (ref "Q3") (pin "1") (pinfunction "G_1") (pintype "passive"))
      (node (ref "R37") (pin "2") (pinfunction "2_2") (pintype "passive"))
      (node (ref "R38") (pin "1") (pinfunction "1_1") (pintype "passive"))
    )
    (net (code "69") (name "Net-(Q4-D)") (class "Default")
      (node (ref "LED7") (pin "C") (pinfunction "C_C") (pintype "passive"))
      (node (ref "Q4") (pin "3") (pinfunction "D_3") (pintype "passive"))
      (node (ref "RELAY4") (pin "P$2") (pinfunction "CATHODE_P$2") (pintype "passive"))
    )
    (net (code "70") (name "Net-(Q4-G)") (class "Default")
      (node (ref "Q4") (pin "1") (pinfunction "G_1") (pintype "passive"))
      (node (ref "R32") (pin "2") (pinfunction "2_2") (pintype "passive"))
      (node (ref "R33") (pin "1") (pinfunction "1_1") (pintype "passive"))
    )
    (net (code "71") (name "Net-(Q5-D)") (class "Default")
      (node (ref "LED9") (pin "C") (pinfunction "C_C") (pintype "passive"))
      (node (ref "Q5") (pin "3") (pinfunction "D_3") (pintype "passive"))
      (node (ref "RELAY5") (pin "P$2") (pinfunction "CATHODE_P$2") (pintype "passive"))
    )
    (net (code "72") (name "Net-(Q5-G)") (class "Default")
      (node (ref "Q5") (pin "1") (pinfunction "G_1") (pintype "passive"))
      (node (ref "R42") (pin "2") (pinfunction "2_2") (pintype "passive"))
      (node (ref "R43") (pin "1") (pinfunction "1_1") (pintype "passive"))
    )
    (net (code "73") (name "Net-(Q6-D)") (class "Default")
      (node (ref "LED10") (pin "C") (pinfunction "C_C") (pintype "passive"))
      (node (ref "Q6") (pin "3") (pinfunction "D_3") (pintype "passive"))
      (node (ref "RELAY6") (pin "P$2") (pinfunction "CATHODE_P$2") (pintype "passive"))
    )
    (net (code "74") (name "Net-(Q6-G)") (class "Default")
      (node (ref "Q6") (pin "1") (pinfunction "G_1") (pintype "passive"))
      (node (ref "R47") (pin "2") (pinfunction "2_2") (pintype "passive"))
      (node (ref "R48") (pin "1") (pinfunction "1_1") (pintype "passive"))
    )
    (net (code "75") (name "Net-(Q7-D)") (class "Default")
      (node (ref "LED11") (pin "C") (pinfunction "C_C") (pintype "passive"))
      (node (ref "Q7") (pin "3") (pinfunction "D_3") (pintype "passive"))
      (node (ref "RELAY7") (pin "P$2") (pinfunction "CATHODE_P$2") (pintype "passive"))
    )
    (net (code "76") (name "Net-(Q7-G)") (class "Default")
      (node (ref "Q7") (pin "1") (pinfunction "G_1") (pintype "passive"))
      (node (ref "R52") (pin "2") (pinfunction "2_2") (pintype "passive"))
      (node (ref "R53") (pin "1") (pinfunction "1_1") (pintype "passive"))
    )
    (net (code "77") (name "Net-(Q8-D)") (class "Default")
      (node (ref "LED12") (pin "C") (pinfunction "C_C") (pintype "passive"))
      (node (ref "Q8") (pin "3") (pinfunction "D_3") (pintype "passive"))
      (node (ref "RELAY8") (pin "P$2") (pinfunction "CATHODE_P$2") (pintype "passive"))
    )
    (net (code "78") (name "Net-(Q8-G)") (class "Default")
      (node (ref "Q8") (pin "1") (pinfunction "G_1") (pintype "passive"))
      (node (ref "R57") (pin "2") (pinfunction "2_2") (pintype "passive"))
      (node (ref "R58") (pin "1") (pinfunction "1_1") (pintype "passive"))
    )
    (net (code "79") (name "Net-(Q9-D)") (class "Default")
      (node (ref "LED13") (pin "C") (pinfunction "C_C") (pintype "passive"))
      (node (ref "Q9") (pin "3") (pinfunction "D_3") (pintype "passive"))
      (node (ref "RELAY9") (pin "P$2") (pinfunction "CATHODE_P$2") (pintype "passive"))
    )
    (net (code "80") (name "Net-(Q9-G)") (class "Default")
      (node (ref "Q9") (pin "1") (pinfunction "G_1") (pintype "passive"))
      (node (ref "R62") (pin "2") (pinfunction "2_2") (pintype "passive"))
      (node (ref "R63") (pin "1") (pinfunction "1_1") (pintype "passive"))
    )
    (net (code "81") (name "Net-(Q10-D)") (class "Default")
      (node (ref "LED14") (pin "C") (pinfunction "C_C") (pintype "passive"))
      (node (ref "Q10") (pin "3") (pinfunction "D_3") (pintype "passive"))
      (node (ref "RELAY10") (pin "P$2") (pinfunction "CATHODE_P$2") (pintype "passive"))
    )
    (net (code "82") (name "Net-(Q10-G)") (class "Default")
      (node (ref "Q10") (pin "1") (pinfunction "G_1") (pintype "passive"))
      (node (ref "R67") (pin "2") (pinfunction "2_2") (pintype "passive"))
      (node (ref "R68") (pin "1") (pinfunction "1_1") (pintype "passive"))
    )
    (net (code "83") (name "Net-(Q11-D)") (class "Default")
      (node (ref "LED16") (pin "C") (pinfunction "C_C") (pintype "passive"))
      (node (ref "Q11") (pin "3") (pinfunction "D_3") (pintype "passive"))
      (node (ref "RELAY11") (pin "P$2") (pinfunction "CATHODE_P$2") (pintype "passive"))
    )
    (net (code "84") (name "Net-(Q11-G)") (class "Default")
      (node (ref "Q11") (pin "1") (pinfunction "G_1") (pintype "passive"))
      (node (ref "R77") (pin "2") (pinfunction "2_2") (pintype "passive"))
      (node (ref "R78") (pin "1") (pinfunction "1_1") (pintype "passive"))
    )
    (net (code "85") (name "Net-(Q12-D)") (class "Default")
      (node (ref "LED15") (pin "C") (pinfunction "C_C") (pintype "passive"))
      (node (ref "Q12") (pin "3") (pinfunction "D_3") (pintype "passive"))
      (node (ref "RELAY12") (pin "P$2") (pinfunction "CATHODE_P$2") (pintype "passive"))
    )
    (net (code "86") (name "Net-(Q12-G)") (class "Default")
      (node (ref "Q12") (pin "1") (pinfunction "G_1") (pintype "passive"))
      (node (ref "R72") (pin "2") (pinfunction "2_2") (pintype "passive"))
      (node (ref "R73") (pin "1") (pinfunction "1_1") (pintype "passive"))
    )
    (net (code "87") (name "Net-(Q13-D)") (class "Default")
      (node (ref "LED17") (pin "C") (pinfunction "C_C") (pintype "passive"))
      (node (ref "Q13") (pin "3") (pinfunction "D_3") (pintype "passive"))
      (node (ref "RELAY13") (pin "P$2") (pinfunction "CATHODE_P$2") (pintype "passive"))
    )
    (net (code "88") (name "Net-(Q13-G)") (class "Default")
      (node (ref "Q13") (pin "1") (pinfunction "G_1") (pintype "passive"))
      (node (ref "R82") (pin "2") (pinfunction "2_2") (pintype "passive"))
      (node (ref "R83") (pin "1") (pinfunction "1_1") (pintype "passive"))
    )
    (net (code "89") (name "Net-(Q14-D)") (class "Default")
      (node (ref "LED18") (pin "C") (pinfunction "C_C") (pintype "passive"))
      (node (ref "Q14") (pin "3") (pinfunction "D_3") (pintype "passive"))
      (node (ref "RELAY14") (pin "P$2") (pinfunction "CATHODE_P$2") (pintype "passive"))
    )
    (net (code "90") (name "Net-(Q14-G)") (class "Default")
      (node (ref "Q14") (pin "1") (pinfunction "G_1") (pintype "passive"))
      (node (ref "R87") (pin "2") (pinfunction "2_2") (pintype "passive"))
      (node (ref "R88") (pin "1") (pinfunction "1_1") (pintype "passive"))
    )
    (net (code "91") (name "Net-(Q15-D)") (class "Default")
      (node (ref "LED19") (pin "C") (pinfunction "C_C") (pintype "passive"))
      (node (ref "Q15") (pin "3") (pinfunction "D_3") (pintype "passive"))
      (node (ref "RELAY15") (pin "P$2") (pinfunction "CATHODE_P$2") (pintype "passive"))
    )
    (net (code "92") (name "Net-(Q15-G)") (class "Default")
      (node (ref "Q15") (pin "1") (pinfunction "G_1") (pintype "passive"))
      (node (ref "R92") (pin "2") (pinfunction "2_2") (pintype "passive"))
      (node (ref "R93") (pin "1") (pinfunction "1_1") (pintype "passive"))
    )
    (net (code "93") (name "Net-(Q16-D)") (class "Default")
      (node (ref "LED21") (pin "C") (pinfunction "C_C") (pintype "passive"))
      (node (ref "Q16") (pin "3") (pinfunction "D_3") (pintype "passive"))
      (node (ref "RELAY16") (pin "P$2") (pinfunction "CATHODE_P$2") (pintype "passive"))
    )
    (net (code "94") (name "Net-(Q16-G)") (class "Default")
      (node (ref "Q16") (pin "1") (pinfunction "G_1") (pintype "passive"))
      (node (ref "R102") (pin "2") (pinfunction "2_2") (pintype "passive"))
      (node (ref "R103") (pin "1") (pinfunction "1_1") (pintype "passive"))
    )
    (net (code "95") (name "Net-(RELAY1-ANODE)") (class "Default")
      (node (ref "R15") (pin "1") (pinfunction "1_1") (pintype "passive"))
      (node (ref "RELAY1") (pin "P$1") (pinfunction "ANODE_P$1") (pintype "passive"))
    )
    (net (code "96") (name "Net-(RELAY2-ANODE)") (class "Default")
      (node (ref "R26") (pin "1") (pinfunction "1_1") (pintype "passive"))
      (node (ref "RELAY2") (pin "P$1") (pinfunction "ANODE_P$1") (pintype "passive"))
    )
    (net (code "97") (name "Net-(RELAY3-ANODE)") (class "Default")
      (node (ref "R36") (pin "1") (pinfunction "1_1") (pintype "passive"))
      (node (ref "RELAY3") (pin "P$1") (pinfunction "ANODE_P$1") (pintype "passive"))
    )
    (net (code "98") (name "Net-(RELAY4-ANODE)") (class "Default")
      (node (ref "R31") (pin "1") (pinfunction "1_1") (pintype "passive"))
      (node (ref "RELAY4") (pin "P$1") (pinfunction "ANODE_P$1") (pintype "passive"))
    )
    (net (code "99") (name "Net-(RELAY5-ANODE)") (class "Default")
      (node (ref "R41") (pin "1") (pinfunction "1_1") (pintype "passive"))
      (node (ref "RELAY5") (pin "P$1") (pinfunction "ANODE_P$1") (pintype "passive"))
    )
    (net (code "100") (name "Net-(RELAY6-ANODE)") (class "Default")
      (node (ref "R46") (pin "1") (pinfunction "1_1") (pintype "passive"))
      (node (ref "RELAY6") (pin "P$1") (pinfunction "ANODE_P$1") (pintype "passive"))
    )
    (net (code "101") (name "Net-(RELAY7-ANODE)") (class "Default")
      (node (ref "R51") (pin "1") (pinfunction "1_1") (pintype "passive"))
      (node (ref "RELAY7") (pin "P$1") (pinfunction "ANODE_P$1") (pintype "passive"))
    )
    (net (code "102") (name "Net-(RELAY8-ANODE)") (class "Default")
      (node (ref "R56") (pin "1") (pinfunction "1_1") (pintype "passive"))
      (node (ref "RELAY8") (pin "P$1") (pinfunction "ANODE_P$1") (pintype "passive"))
    )
    (net (code "103") (name "Net-(RELAY9-ANODE)") (class "Default")
      (node (ref "R61") (pin "1") (pinfunction "1_1") (pintype "passive"))
      (node (ref "RELAY9") (pin "P$1") (pinfunction "ANODE_P$1") (pintype "passive"))
    )
    (net (code "104") (name "Net-(RELAY10-ANODE)") (class "Default")
      (node (ref "R66") (pin "1") (pinfunction "1_1") (pintype "passive"))
      (node (ref "RELAY10") (pin "P$1") (pinfunction "ANODE_P$1") (pintype "passive"))
    )
    (net (code "105") (name "Net-(RELAY11-ANODE)") (class "Default")
      (node (ref "R76") (pin "1") (pinfunction "1_1") (pintype "passive"))
      (node (ref "RELAY11") (pin "P$1") (pinfunction "ANODE_P$1") (pintype "passive"))
    )
    (net (code "106") (name "Net-(RELAY12-ANODE)") (class "Default")
      (node (ref "R71") (pin "1") (pinfunction "1_1") (pintype "passive"))
      (node (ref "RELAY12") (pin "P$1") (pinfunction "ANODE_P$1") (pintype "passive"))
    )
    (net (code "107") (name "Net-(RELAY13-ANODE)") (class "Default")
      (node (ref "R81") (pin "1") (pinfunction "1_1") (pintype "passive"))
      (node (ref "RELAY13") (pin "P$1") (pinfunction "ANODE_P$1") (pintype "passive"))
    )
    (net (code "108") (name "Net-(RELAY14-ANODE)") (class "Default")
      (node (ref "R86") (pin "1") (pinfunction "1_1") (pintype "passive"))
      (node (ref "RELAY14") (pin "P$1") (pinfunction "ANODE_P$1") (pintype "passive"))
    )
    (net (code "109") (name "Net-(RELAY15-ANODE)") (class "Default")
      (node (ref "R91") (pin "1") (pinfunction "1_1") (pintype "passive"))
      (node (ref "RELAY15") (pin "P$1") (pinfunction "ANODE_P$1") (pintype "passive"))
    )
    (net (code "110") (name "Net-(RELAY16-ANODE)") (class "Default")
      (node (ref "R101") (pin "1") (pinfunction "1_1") (pintype "passive"))
      (node (ref "RELAY16") (pin "P$1") (pinfunction "ANODE_P$1") (pintype "passive"))
    )
    (net (code "111") (name "Net-(U2-BYPASS)") (class "Default")
      (node (ref "C6") (pin "1") (pinfunction "1_1") (pintype "passive"))
      (node (ref "U2") (pin "4") (pinfunction "BYPASS_4") (pintype "bidirectional"))
    )
    (net (code "112") (name "RELAY1") (class "Default")
      (node (ref "IC1") (pin "14") (pinfunction "PB0_14") (pintype "bidirectional"))
      (node (ref "R17") (pin "2") (pinfunction "2_2") (pintype "passive"))
    )
    (net (code "113") (name "RELAY2") (class "Default")
      (node (ref "IC1") (pin "13") (pinfunction "PA7_13") (pintype "bidirectional"))
      (node (ref "R28") (pin "2") (pinfunction "2_2") (pintype "passive"))
    )
    (net (code "114") (name "RELAY3") (class "Default")
      (node (ref "IC1") (pin "12") (pinfunction "PA6_12") (pintype "bidirectional"))
      (node (ref "R38") (pin "2") (pinfunction "2_2") (pintype "passive"))
    )
    (net (code "115") (name "RELAY4") (class "Default")
      (node (ref "IC1") (pin "11") (pinfunction "PA5_11") (pintype "bidirectional"))
      (node (ref "R33") (pin "2") (pinfunction "2_2") (pintype "passive"))
    )
    (net (code "116") (name "RELAY5") (class "Default")
      (node (ref "IC1") (pin "10") (pinfunction "PA4_10") (pintype "bidirectional"))
      (node (ref "R43") (pin "2") (pinfunction "2_2") (pintype "passive"))
    )
    (net (code "117") (name "RELAY6") (class "Default")
      (node (ref "IC1") (pin "9") (pinfunction "PA3_9") (pintype "bidirectional"))
      (node (ref "R48") (pin "2") (pinfunction "2_2") (pintype "passive"))
    )
    (net (code "118") (name "RELAY7") (class "Default")
      (node (ref "IC1") (pin "8") (pinfunction "PA2_8") (pintype "bidirectional"))
      (node (ref "R53") (pin "2") (pinfunction "2_2") (pintype "passive"))
    )
    (net (code "119") (name "RELAY8") (class "Default")
      (node (ref "IC1") (pin "7") (pinfunction "PA1_7") (pintype "bidirectional"))
      (node (ref "R58") (pin "2") (pinfunction "2_2") (pintype "passive"))
    )
    (net (code "120") (name "RELAY9") (class "Default")
      (node (ref "IC1") (pin "15") (pinfunction "PB1_15") (pintype "bidirectional"))
      (node (ref "R63") (pin "2") (pinfunction "2_2") (pintype "passive"))
    )
    (net (code "121") (name "RELAY10") (class "Default")
      (node (ref "IC1") (pin "18") (pinfunction "PA8_18") (pintype "bidirectional"))
      (node (ref "R68") (pin "2") (pinfunction "2_2") (pintype "passive"))
    )
    (net (code "122") (name "RELAY11") (class "Default")
      (node (ref "IC1") (pin "19") (pinfunction "PA9_19") (pintype "bidirectional"))
      (node (ref "R78") (pin "2") (pinfunction "2_2") (pintype "passive"))
    )
    (net (code "123") (name "RELAY12") (class "Default")
      (node (ref "IC1") (pin "20") (pinfunction "PA10_20") (pintype "bidirectional"))
      (node (ref "R73") (pin "2") (pinfunction "2_2") (pintype "passive"))
    )
    (net (code "124") (name "RELAY13") (class "Default")
      (node (ref "IC1") (pin "28") (pinfunction "PB5_28") (pintype "bidirectional"))
      (node (ref "R83") (pin "2") (pinfunction "2_2") (pintype "passive"))
    )
    (net (code "125") (name "RELAY14") (class "Default")
      (node (ref "IC1") (pin "27") (pinfunction "PB4_27") (pintype "bidirectional"))
      (node (ref "R88") (pin "2") (pinfunction "2_2") (pintype "passive"))
    )
    (net (code "126") (name "RELAY15") (class "Default")
      (node (ref "IC1") (pin "26") (pinfunction "PB3_26") (pintype "bidirectional"))
      (node (ref "R93") (pin "2") (pinfunction "2_2") (pintype "passive"))
    )
    (net (code "127") (name "RELAY16") (class "Default")
      (node (ref "IC1") (pin "25") (pinfunction "PA15_25") (pintype "bidirectional"))
      (node (ref "R103") (pin "2") (pinfunction "2_2") (pintype "passive"))
    )
    (net (code "128") (name "SCL") (class "Default")
      (node (ref "IC1") (pin "29") (pinfunction "PB6_29") (pintype "bidirectional"))
      (node (ref "IC3") (pin "3") (pinfunction "SCL1_3") (pintype "bidirectional"))
      (node (ref "R3") (pin "1") (pinfunction "1_1") (pintype "passive"))
    )
    (net (code "129") (name "SCLISO") (class "Default")
      (node (ref "IC3") (pin "6") (pinfunction "SCL2_6") (pintype "bidirectional"))
      (node (ref "MONITOR1") (pin "5") (pinfunction "SCL_5") (pintype "input"))
      (node (ref "MONITOR10") (pin "5") (pinfunction "SCL_5") (pintype "input"))
      (node (ref "MONITOR11") (pin "5") (pinfunction "SCL_5") (pintype "input"))
      (node (ref "MONITOR12") (pin "2") (pinfunction "A0_2") (pintype "input"))
      (node (ref "MONITOR12") (pin "5") (pinfunction "SCL_5") (pintype "input"))
      (node (ref "MONITOR13") (pin "1") (pinfunction "A1_1") (pintype "input"))
      (node (ref "MONITOR13") (pin "5") (pinfunction "SCL_5") (pintype "input"))
      (node (ref "MONITOR14") (pin "1") (pinfunction "A1_1") (pintype "input"))
      (node (ref "MONITOR14") (pin "5") (pinfunction "SCL_5") (pintype "input"))
      (node (ref "MONITOR15") (pin "1") (pinfunction "A1_1") (pintype "input"))
      (node (ref "MONITOR15") (pin "5") (pinfunction "SCL_5") (pintype "input"))
      (node (ref "MONITOR16") (pin "1") (pinfunction "A1_1") (pintype "input"))
      (node (ref "MONITOR16") (pin "2") (pinfunction "A0_2") (pintype "input"))
      (node (ref "MONITOR16") (pin "5") (pinfunction "SCL_5") (pintype "input"))
      (node (ref "MONITOR2") (pin "5") (pinfunction "SCL_5") (pintype "input"))
      (node (ref "MONITOR3") (pin "5") (pinfunction "SCL_5") (pintype "input"))
      (node (ref "MONITOR4") (pin "2") (pinfunction "A0_2") (pintype "input"))
      (node (ref "MONITOR4") (pin "5") (pinfunction "SCL_5") (pintype "input"))
      (node (ref "MONITOR5") (pin "5") (pinfunction "SCL_5") (pintype "input"))
      (node (ref "MONITOR6") (pin "5") (pinfunction "SCL_5") (pintype "input"))
      (node (ref "MONITOR7") (pin "5") (pinfunction "SCL_5") (pintype "input"))
      (node (ref "MONITOR8") (pin "2") (pinfunction "A0_2") (pintype "input"))
      (node (ref "MONITOR8") (pin "5") (pinfunction "SCL_5") (pintype "input"))
      (node (ref "MONITOR9") (pin "5") (pinfunction "SCL_5") (pintype "input"))
      (node (ref "R6") (pin "1") (pinfunction "1_1") (pintype "passive"))
    )
    (net (code "130") (name "SDA") (class "Default")
      (node (ref "IC1") (pin "30") (pinfunction "PB7_30") (pintype "bidirectional"))
      (node (ref "IC3") (pin "2") (pinfunction "SDA1_2") (pintype "bidirectional"))
      (node (ref "R4") (pin "1") (pinfunction "1_1") (pintype "passive"))
    )
    (net (code "131") (name "SDAISO") (class "Default")
      (node (ref "IC3") (pin "7") (pinfunction "SDA2_7") (pintype "bidirectional"))
      (node (ref "MONITOR1") (pin "4") (pinfunction "SDA_4") (pintype "bidirectional"))
      (node (ref "MONITOR10") (pin "1") (pinfunction "A1_1") (pintype "input"))
      (node (ref "MONITOR10") (pin "4") (pinfunction "SDA_4") (pintype "bidirectional"))
      (node (ref "MONITOR11") (pin "1") (pinfunction "A1_1") (pintype "input"))
      (node (ref "MONITOR11") (pin "2") (pinfunction "A0_2") (pintype "input"))
      (node (ref "MONITOR11") (pin "4") (pinfunction "SDA_4") (pintype "bidirectional"))
      (node (ref "MONITOR12") (pin "1") (pinfunction "A1_1") (pintype "input"))
      (node (ref "MONITOR12") (pin "4") (pinfunction "SDA_4") (pintype "bidirectional"))
      (node (ref "MONITOR13") (pin "4") (pinfunction "SDA_4") (pintype "bidirectional"))
      (node (ref "MONITOR14") (pin "4") (pinfunction "SDA_4") (pintype "bidirectional"))
      (node (ref "MONITOR15") (pin "2") (pinfunction "A0_2") (pintype "input"))
      (node (ref "MONITOR15") (pin "4") (pinfunction "SDA_4") (pintype "bidirectional"))
      (node (ref "MONITOR16") (pin "4") (pinfunction "SDA_4") (pintype "bidirectional"))
      (node (ref "MONITOR2") (pin "4") (pinfunction "SDA_4") (pintype "bidirectional"))
      (node (ref "MONITOR3") (pin "2") (pinfunction "A0_2") (pintype "input"))
      (node (ref "MONITOR3") (pin "4") (pinfunction "SDA_4") (pintype "bidirectional"))
      (node (ref "MONITOR4") (pin "4") (pinfunction "SDA_4") (pintype "bidirectional"))
      (node (ref "MONITOR5") (pin "4") (pinfunction "SDA_4") (pintype "bidirectional"))
      (node (ref "MONITOR6") (pin "4") (pinfunction "SDA_4") (pintype "bidirectional"))
      (node (ref "MONITOR7") (pin "2") (pinfunction "A0_2") (pintype "input"))
      (node (ref "MONITOR7") (pin "4") (pinfunction "SDA_4") (pintype "bidirectional"))
      (node (ref "MONITOR8") (pin "4") (pinfunction "SDA_4") (pintype "bidirectional"))
      (node (ref "MONITOR9") (pin "1") (pinfunction "A1_1") (pintype "input"))
      (node (ref "MONITOR9") (pin "4") (pinfunction "SDA_4") (pintype "bidirectional"))
      (node (ref "R5") (pin "1") (pinfunction "1_1") (pintype "passive"))
    )
    (net (code "132") (name "STATUS") (class "Default")
      (node (ref "IC1") (pin "3") (pinfunction "PC15-OSC32_OUT_3") (pintype "bidirectional"))
      (node (ref "LED1") (pin "C1") (pinfunction "C_C1") (pintype "passive"))
      (node (ref "R13") (pin "2") (pinfunction "2_2") (pintype "passive"))
    )
    (net (code "133") (name "SWCLK") (class "Default")
      (node (ref "IC1") (pin "24") (pinfunction "PA14_24") (pintype "bidirectional"))
      (node (ref "J2") (pin "4") (pinfunction "4_4") (pintype "passive"))
    )
    (net (code "134") (name "SWDIO") (class "Default")
      (node (ref "IC1") (pin "23") (pinfunction "PA13_23") (pintype "bidirectional"))
      (node (ref "J2") (pin "2") (pinfunction "2_2") (pintype "passive"))
    )
    (net (code "135") (name "USB_DM") (class "Default")
      (node (ref "IC1") (pin "21") (pinfunction "PA11_21") (pintype "bidirectional"))
      (node (ref "U1") (pin "6") (pinfunction "6_6") (pintype "bidirectional"))
    )
    (net (code "136") (name "USB_DP") (class "Default")
      (node (ref "IC1") (pin "22") (pinfunction "PA12_22") (pintype "bidirectional"))
      (node (ref "U1") (pin "4") (pinfunction "4_4") (pintype "bidirectional"))
    )
    (net (code "137") (name "VBUS") (class "Default")
      (node (ref "C1") (pin "1") (pinfunction "1_1") (pintype "passive"))
      (node (ref "C2") (pin "1") (pinfunction "1_1") (pintype "passive"))
      (node (ref "C4") (pin "1") (pinfunction "1_1") (pintype "passive"))
      (node (ref "F2") (pin "1") (pinfunction "1_1") (pintype "passive"))
      (node (ref "IC2") (pin "2") (pinfunction "VIN_2") (pintype "power_in"))
      (node (ref "R100") (pin "2") (pinfunction "2_2") (pintype "passive"))
      (node (ref "R101") (pin "2") (pinfunction "2_2") (pintype "passive"))
      (node (ref "R14") (pin "2") (pinfunction "2_2") (pintype "passive"))
      (node (ref "R15") (pin "2") (pinfunction "2_2") (pintype "passive"))
      (node (ref "R25") (pin "2") (pinfunction "2_2") (pintype "passive"))
      (node (ref "R26") (pin "2") (pinfunction "2_2") (pintype "passive"))
      (node (ref "R30") (pin "2") (pinfunction "2_2") (pintype "passive"))
      (node (ref "R31") (pin "2") (pinfunction "2_2") (pintype "passive"))
      (node (ref "R35") (pin "2") (pinfunction "2_2") (pintype "passive"))
      (node (ref "R36") (pin "2") (pinfunction "2_2") (pintype "passive"))
      (node (ref "R40") (pin "2") (pinfunction "2_2") (pintype "passive"))
      (node (ref "R41") (pin "2") (pinfunction "2_2") (pintype "passive"))
      (node (ref "R45") (pin "2") (pinfunction "2_2") (pintype "passive"))
      (node (ref "R46") (pin "2") (pinfunction "2_2") (pintype "passive"))
      (node (ref "R50") (pin "2") (pinfunction "2_2") (pintype "passive"))
      (node (ref "R51") (pin "2") (pinfunction "2_2") (pintype "passive"))
      (node (ref "R55") (pin "2") (pinfunction "2_2") (pintype "passive"))
      (node (ref "R56") (pin "2") (pinfunction "2_2") (pintype "passive"))
      (node (ref "R60") (pin "2") (pinfunction "2_2") (pintype "passive"))
      (node (ref "R61") (pin "2") (pinfunction "2_2") (pintype "passive"))
      (node (ref "R65") (pin "2") (pinfunction "2_2") (pintype "passive"))
      (node (ref "R66") (pin "2") (pinfunction "2_2") (pintype "passive"))
      (node (ref "R70") (pin "2") (pinfunction "2_2") (pintype "passive"))
      (node (ref "R71") (pin "2") (pinfunction "2_2") (pintype "passive"))
      (node (ref "R75") (pin "2") (pinfunction "2_2") (pintype "passive"))
      (node (ref "R76") (pin "2") (pinfunction "2_2") (pintype "passive"))
      (node (ref "R80") (pin "2") (pinfunction "2_2") (pintype "passive"))
      (node (ref "R81") (pin "2") (pinfunction "2_2") (pintype "passive"))
      (node (ref "R85") (pin "2") (pinfunction "2_2") (pintype "passive"))
      (node (ref "R86") (pin "2") (pinfunction "2_2") (pintype "passive"))
      (node (ref "R90") (pin "2") (pinfunction "2_2") (pintype "passive"))
      (node (ref "R91") (pin "2") (pinfunction "2_2") (pintype "passive"))
      (node (ref "U2") (pin "1") (pinfunction "IN_1") (pintype "bidirectional"))
      (node (ref "U2") (pin "3") (pinfunction "ON/OFF_3") (pintype "bidirectional"))
    )
    (net (code "138") (name "VCC") (class "Default")
      (node (ref "C10") (pin "1") (pinfunction "1_1") (pintype "passive"))
      (node (ref "C11") (pin "1") (pinfunction "1_1") (pintype "passive"))
      (node (ref "C12") (pin "1") (pinfunction "1_1") (pintype "passive"))
      (node (ref "C14") (pin "1") (pinfunction "1_1") (pintype "passive"))
      (node (ref "C5") (pin "1") (pinfunction "1_1") (pintype "passive"))
      (node (ref "C7") (pin "1") (pinfunction "1_1") (pintype "passive"))
      (node (ref "IC1") (pin "1") (pinfunction "VDD_1") (pintype "bidirectional"))
      (node (ref "IC1") (pin "17") (pinfunction "VDD_17") (pintype "bidirectional"))
      (node (ref "IC1") (pin "5") (pinfunction "VDDA/VREF+_5") (pintype "bidirectional"))
      (node (ref "IC3") (pin "1") (pinfunction "VCC1_1") (pintype "bidirectional"))
      (node (ref "J2") (pin "1") (pinfunction "1_1") (pintype "passive"))
      (node (ref "R11") (pin "2") (pinfunction "2_2") (pintype "passive"))
      (node (ref "R12") (pin "2") (pinfunction "2_2") (pintype "passive"))
      (node (ref "R3") (pin "2") (pinfunction "2_2") (pintype "passive"))
      (node (ref "R4") (pin "2") (pinfunction "2_2") (pintype "passive"))
      (node (ref "R8") (pin "2") (pinfunction "2_2") (pintype "passive"))
      (node (ref "U2") (pin "5") (pinfunction "OUT_5") (pintype "bidirectional"))
    )
    (net (code "139") (name "VCCISO") (class "Default")
      (node (ref "C13") (pin "1") (pinfunction "1_1") (pintype "passive"))
      (node (ref "C15") (pin "1") (pinfunction "1_1") (pintype "passive"))
      (node (ref "C16") (pin "1") (pinfunction "1_1") (pintype "passive"))
      (node (ref "C17") (pin "1") (pinfunction "1_1") (pintype "passive"))
      (node (ref "C18") (pin "1") (pinfunction "1_1") (pintype "passive"))
      (node (ref "C19") (pin "1") (pinfunction "1_1") (pintype "passive"))
      (node (ref "C20") (pin "1") (pinfunction "1_1") (pintype "passive"))
      (node (ref "C21") (pin "1") (pinfunction "1_1") (pintype "passive"))
      (node (ref "C22") (pin "1") (pinfunction "1_1") (pintype "passive"))
      (node (ref "C23") (pin "1") (pinfunction "1_1") (pintype "passive"))
      (node (ref "C24") (pin "1") (pinfunction "1_1") (pintype "passive"))
      (node (ref "C25") (pin "1") (pinfunction "1_1") (pintype "passive"))
      (node (ref "C26") (pin "1") (pinfunction "1_1") (pintype "passive"))
      (node (ref "C27") (pin "1") (pinfunction "1_1") (pintype "passive"))
      (node (ref "C28") (pin "1") (pinfunction "1_1") (pintype "passive"))
      (node (ref "C3") (pin "1") (pinfunction "1_1") (pintype "passive"))
      (node (ref "C30") (pin "1") (pinfunction "1_1") (pintype "passive"))
      (node (ref "C8") (pin "1") (pinfunction "1_1") (pintype "passive"))
      (node (ref "F1") (pin "2") (pinfunction "2_2") (pintype "passive"))
      (node (ref "IC3") (pin "8") (pinfunction "VCC2_8") (pintype "bidirectional"))
      (node (ref "MONITOR1") (pin "6") (pinfunction "VS_6") (pintype "power_in"))
      (node (ref "MONITOR10") (pin "2") (pinfunction "A0_2") (pintype "input"))
      (node (ref "MONITOR10") (pin "6") (pinfunction "VS_6") (pintype "power_in"))
      (node (ref "MONITOR11") (pin "6") (pinfunction "VS_6") (pintype "power_in"))
      (node (ref "MONITOR12") (pin "6") (pinfunction "VS_6") (pintype "power_in"))
      (node (ref "MONITOR13") (pin "6") (pinfunction "VS_6") (pintype "power_in"))
      (node (ref "MONITOR14") (pin "2") (pinfunction "A0_2") (pintype "input"))
      (node (ref "MONITOR14") (pin "6") (pinfunction "VS_6") (pintype "power_in"))
      (node (ref "MONITOR15") (pin "6") (pinfunction "VS_6") (pintype "power_in"))
      (node (ref "MONITOR16") (pin "6") (pinfunction "VS_6") (pintype "power_in"))
      (node (ref "MONITOR2") (pin "2") (pinfunction "A0_2") (pintype "input"))
      (node (ref "MONITOR2") (pin "6") (pinfunction "VS_6") (pintype "power_in"))
      (node (ref "MONITOR3") (pin "6") (pinfunction "VS_6") (pintype "power_in"))
      (node (ref "MONITOR4") (pin "6") (pinfunction "VS_6") (pintype "power_in"))
      (node (ref "MONITOR5") (pin "1") (pinfunction "A1_1") (pintype "input"))
      (node (ref "MONITOR5") (pin "6") (pinfunction "VS_6") (pintype "power_in"))
      (node (ref "MONITOR6") (pin "1") (pinfunction "A1_1") (pintype "input"))
      (node (ref "MONITOR6") (pin "2") (pinfunction "A0_2") (pintype "input"))
      (node (ref "MONITOR6") (pin "6") (pinfunction "VS_6") (pintype "power_in"))
      (node (ref "MONITOR7") (pin "1") (pinfunction "A1_1") (pintype "input"))
      (node (ref "MONITOR7") (pin "6") (pinfunction "VS_6") (pintype "power_in"))
      (node (ref "MONITOR8") (pin "1") (pinfunction "A1_1") (pintype "input"))
      (node (ref "MONITOR8") (pin "6") (pinfunction "VS_6") (pintype "power_in"))
      (node (ref "MONITOR9") (pin "6") (pinfunction "VS_6") (pintype "power_in"))
      (node (ref "R10") (pin "2") (pinfunction "2_2") (pintype "passive"))
      (node (ref "R19") (pin "2") (pinfunction "2_2") (pintype "passive"))
      (node (ref "R5") (pin "2") (pinfunction "2_2") (pintype "passive"))
      (node (ref "R6") (pin "2") (pinfunction "2_2") (pintype "passive"))
      (node (ref "R7") (pin "2") (pinfunction "2_2") (pintype "passive"))
      (node (ref "R9") (pin "1") (pinfunction "1_1") (pintype "passive"))
    )
    (net (code "140") (name "VIN1") (class "Default")
      (node (ref "RELAY1") (pin "P$4") (pinfunction "DRAIN2_P$4") (pintype "passive"))
      (node (ref "X1") (pin "2") (pinfunction "4_2") (pintype "passive"))
    )
    (net (code "141") (name "VIN2") (class "Default")
      (node (ref "RELAY2") (pin "P$4") (pinfunction "DRAIN2_P$4") (pintype "passive"))
      (node (ref "X2") (pin "2") (pinfunction "4_2") (pintype "passive"))
    )
    (net (code "142") (name "VIN3") (class "Default")
      (node (ref "RELAY3") (pin "P$4") (pinfunction "DRAIN2_P$4") (pintype "passive"))
      (node (ref "X3") (pin "2") (pinfunction "4_2") (pintype "passive"))
    )
    (net (code "143") (name "VIN4") (class "Default")
      (node (ref "RELAY4") (pin "P$4") (pinfunction "DRAIN2_P$4") (pintype "passive"))
      (node (ref "X4") (pin "2") (pinfunction "4_2") (pintype "passive"))
    )
    (net (code "144") (name "VIN5") (class "Default")
      (node (ref "RELAY5") (pin "P$4") (pinfunction "DRAIN2_P$4") (pintype "passive"))
      (node (ref "X5") (pin "2") (pinfunction "4_2") (pintype "passive"))
    )
    (net (code "145") (name "VIN6") (class "Default")
      (node (ref "RELAY6") (pin "P$4") (pinfunction "DRAIN2_P$4") (pintype "passive"))
      (node (ref "X6") (pin "2") (pinfunction "4_2") (pintype "passive"))
    )
    (net (code "146") (name "VIN7") (class "Default")
      (node (ref "RELAY7") (pin "P$4") (pinfunction "DRAIN2_P$4") (pintype "passive"))
      (node (ref "X7") (pin "2") (pinfunction "4_2") (pintype "passive"))
    )
    (net (code "147") (name "VIN8") (class "Default")
      (node (ref "RELAY8") (pin "P$4") (pinfunction "DRAIN2_P$4") (pintype "passive"))
      (node (ref "X8") (pin "2") (pinfunction "4_2") (pintype "passive"))
    )
    (net (code "148") (name "VIN9") (class "Default")
      (node (ref "RELAY9") (pin "P$4") (pinfunction "DRAIN2_P$4") (pintype "passive"))
      (node (ref "X9") (pin "2") (pinfunction "4_2") (pintype "passive"))
    )
    (net (code "149") (name "VIN10") (class "Default")
      (node (ref "RELAY10") (pin "P$4") (pinfunction "DRAIN2_P$4") (pintype "passive"))
      (node (ref "X10") (pin "2") (pinfunction "4_2") (pintype "passive"))
    )
    (net (code "150") (name "VIN11") (class "Default")
      (node (ref "RELAY11") (pin "P$4") (pinfunction "DRAIN2_P$4") (pintype "passive"))
      (node (ref "X11") (pin "2") (pinfunction "4_2") (pintype "passive"))
    )
    (net (code "151") (name "VIN12") (class "Default")
      (node (ref "RELAY12") (pin "P$4") (pinfunction "DRAIN2_P$4") (pintype "passive"))
      (node (ref "X12") (pin "2") (pinfunction "4_2") (pintype "passive"))
    )
    (net (code "152") (name "VIN13") (class "Default")
      (node (ref "RELAY13") (pin "P$4") (pinfunction "DRAIN2_P$4") (pintype "passive"))
      (node (ref "X13") (pin "2") (pinfunction "4_2") (pintype "passive"))
    )
    (net (code "153") (name "VIN14") (class "Default")
      (node (ref "RELAY14") (pin "P$4") (pinfunction "DRAIN2_P$4") (pintype "passive"))
      (node (ref "X14") (pin "2") (pinfunction "4_2") (pintype "passive"))
    )
    (net (code "154") (name "VIN15") (class "Default")
      (node (ref "RELAY15") (pin "P$4") (pinfunction "DRAIN2_P$4") (pintype "passive"))
      (node (ref "X15") (pin "2") (pinfunction "4_2") (pintype "passive"))
    )
    (net (code "155") (name "VIN16") (class "Default")
      (node (ref "RELAY16") (pin "P$4") (pinfunction "DRAIN2_P$4") (pintype "passive"))
      (node (ref "X16") (pin "2") (pinfunction "4_2") (pintype "passive"))
    )
    (net (code "156") (name "unconnected-(IC1-PA0-CK_IN-Pad6)") (class "Default")
      (node (ref "IC1") (pin "6") (pinfunction "PA0-CK_IN_6") (pintype "bidirectional"))
    )
    (net (code "157") (name "unconnected-(J1-Pad4)") (class "Default")
      (node (ref "J1") (pin "4") (pinfunction "4_4") (pintype "passive"))
    )
    (net (code "158") (name "unconnected-(J2-Pad6)") (class "Default")
      (node (ref "J2") (pin "6") (pinfunction "6_6") (pintype "passive"))
    )
    (net (code "159") (name "unconnected-(J2-Pad7)") (class "Default")
      (node (ref "J2") (pin "7") (pinfunction "7_7") (pintype "passive"))
    )
    (net (code "160") (name "unconnected-(J2-Pad8)") (class "Default")
      (node (ref "J2") (pin "8") (pinfunction "8_8") (pintype "passive"))
    )
    (net (code "161") (name "unconnected-(J2-Pad9)") (class "Default")
      (node (ref "J2") (pin "9") (pinfunction "9_9") (pintype "passive"))
    )
    (net (code "162") (name "unconnected-(S1-Pad1)") (class "Default")
      (node (ref "S1") (pin "1") (pinfunction "1_1") (pintype "passive"))
    )
    (net (code "163") (name "~{ALERTISO}") (class "Default")
      (node (ref "IC4") (pin "2") (pinfunction "CATHODE_2") (pintype "passive"))
      (node (ref "MONITOR1") (pin "3") (pinfunction "ALERT_3") (pintype "open_collector"))
      (node (ref "MONITOR10") (pin "3") (pinfunction "ALERT_3") (pintype "open_collector"))
      (node (ref "MONITOR11") (pin "3") (pinfunction "ALERT_3") (pintype "open_collector"))
      (node (ref "MONITOR12") (pin "3") (pinfunction "ALERT_3") (pintype "open_collector"))
      (node (ref "MONITOR13") (pin "3") (pinfunction "ALERT_3") (pintype "open_collector"))
      (node (ref "MONITOR14") (pin "3") (pinfunction "ALERT_3") (pintype "open_collector"))
      (node (ref "MONITOR15") (pin "3") (pinfunction "ALERT_3") (pintype "open_collector"))
      (node (ref "MONITOR16") (pin "3") (pinfunction "ALERT_3") (pintype "open_collector"))
      (node (ref "MONITOR2") (pin "3") (pinfunction "ALERT_3") (pintype "open_collector"))
      (node (ref "MONITOR3") (pin "3") (pinfunction "ALERT_3") (pintype "open_collector"))
      (node (ref "MONITOR4") (pin "3") (pinfunction "ALERT_3") (pintype "open_collector"))
      (node (ref "MONITOR5") (pin "3") (pinfunction "ALERT_3") (pintype "open_collector"))
      (node (ref "MONITOR6") (pin "3") (pinfunction "ALERT_3") (pintype "open_collector"))
      (node (ref "MONITOR7") (pin "3") (pinfunction "ALERT_3") (pintype "open_collector"))
      (node (ref "MONITOR8") (pin "3") (pinfunction "ALERT_3") (pintype "open_collector"))
      (node (ref "MONITOR9") (pin "3") (pinfunction "ALERT_3") (pintype "open_collector"))
      (node (ref "R19") (pin "1") (pinfunction "1_1") (pintype "passive"))
    )
    (net (code "164") (name "~{ALERT}") (class "Default")
      (node (ref "C9") (pin "1") (pinfunction "1_1") (pintype "passive"))
      (node (ref "IC1") (pin "2") (pinfunction "PC14-OSC32_IN_2") (pintype "bidirectional"))
      (node (ref "IC4") (pin "4") (pinfunction "COLLECTOR_4") (pintype "passive"))
      (node (ref "R8") (pin "1") (pinfunction "1_1") (pintype "passive"))
    )
    (net (code "165") (name "~{NRST}") (class "Default")
      (node (ref "IC1") (pin "4") (pinfunction "~{NRST}_4") (pintype "bidirectional"))
      (node (ref "J2") (pin "10") (pinfunction "10_10") (pintype "passive"))
    )
  )
)
